# MOTOR_DRIVER.net
KiCad netlist of a schematic drawn in EAGLE
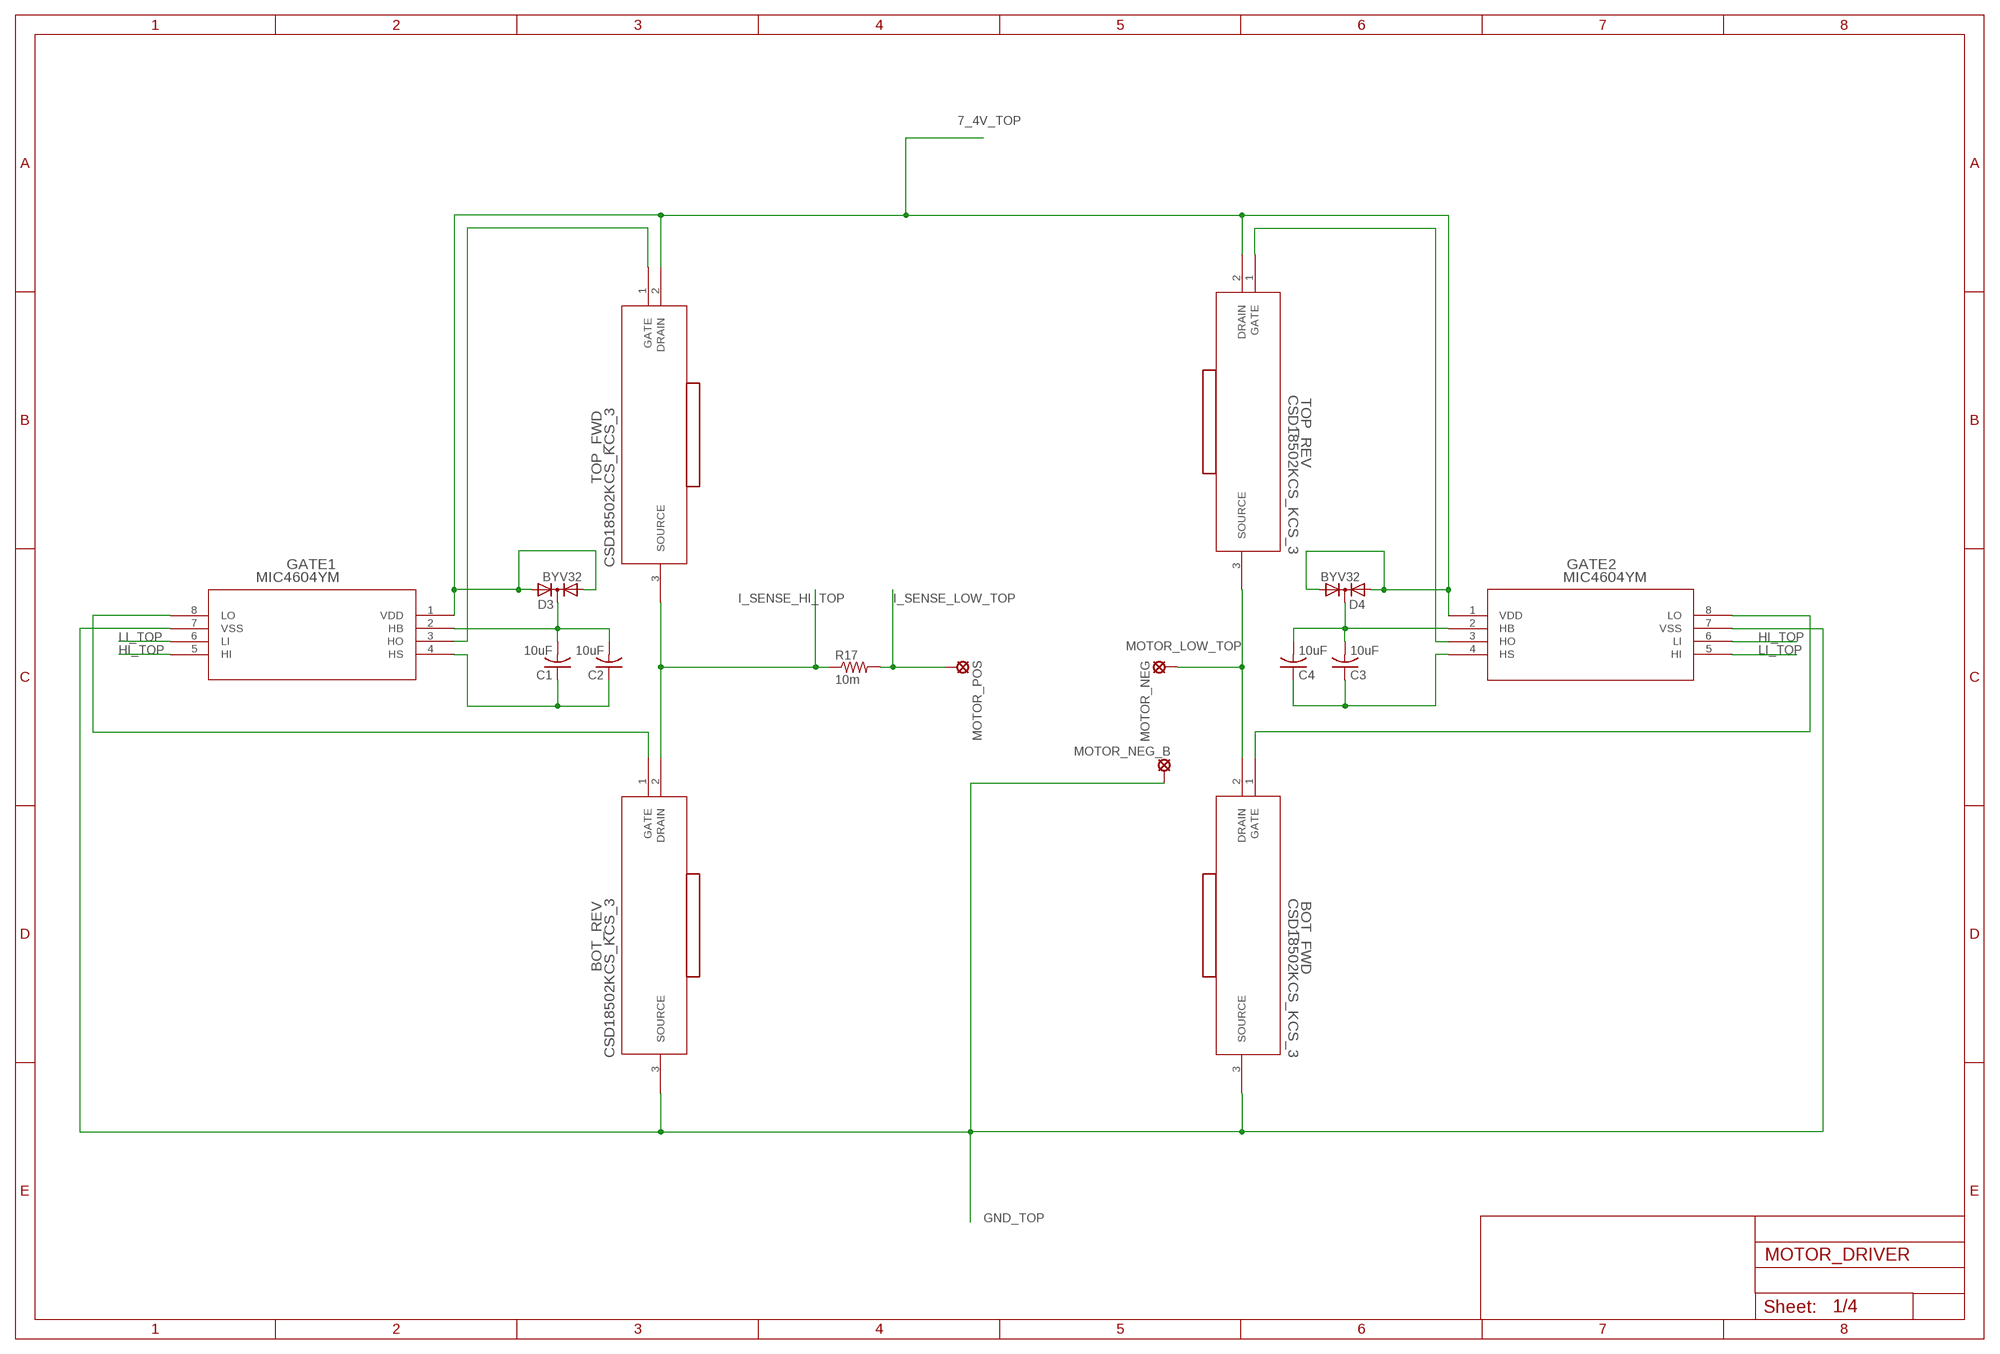
[diagram p0: schematic, sheet 1]
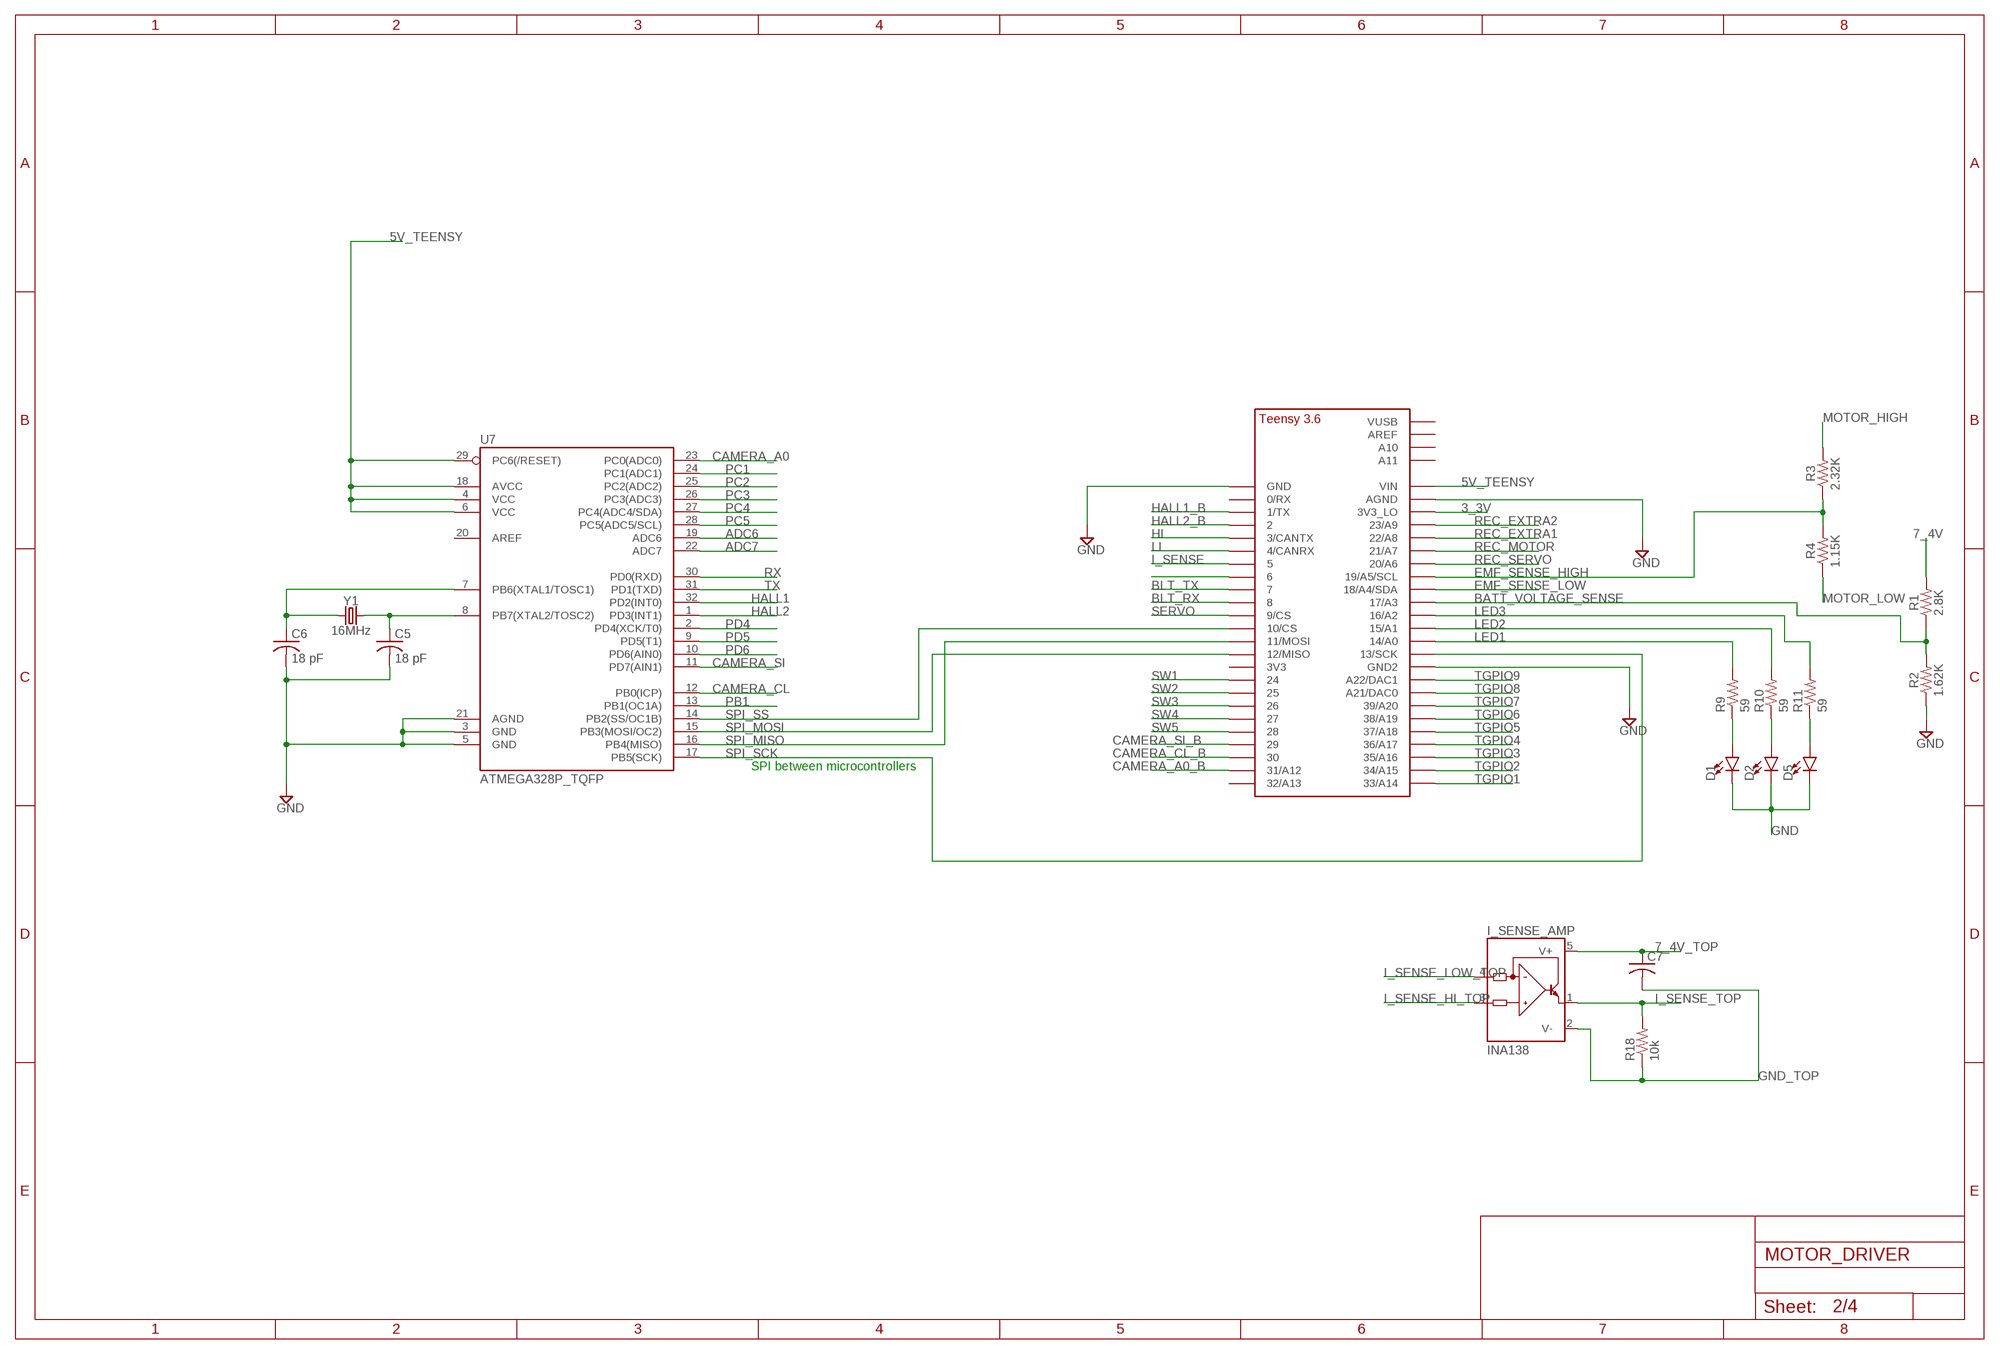
[diagram p1: schematic, sheet 2]
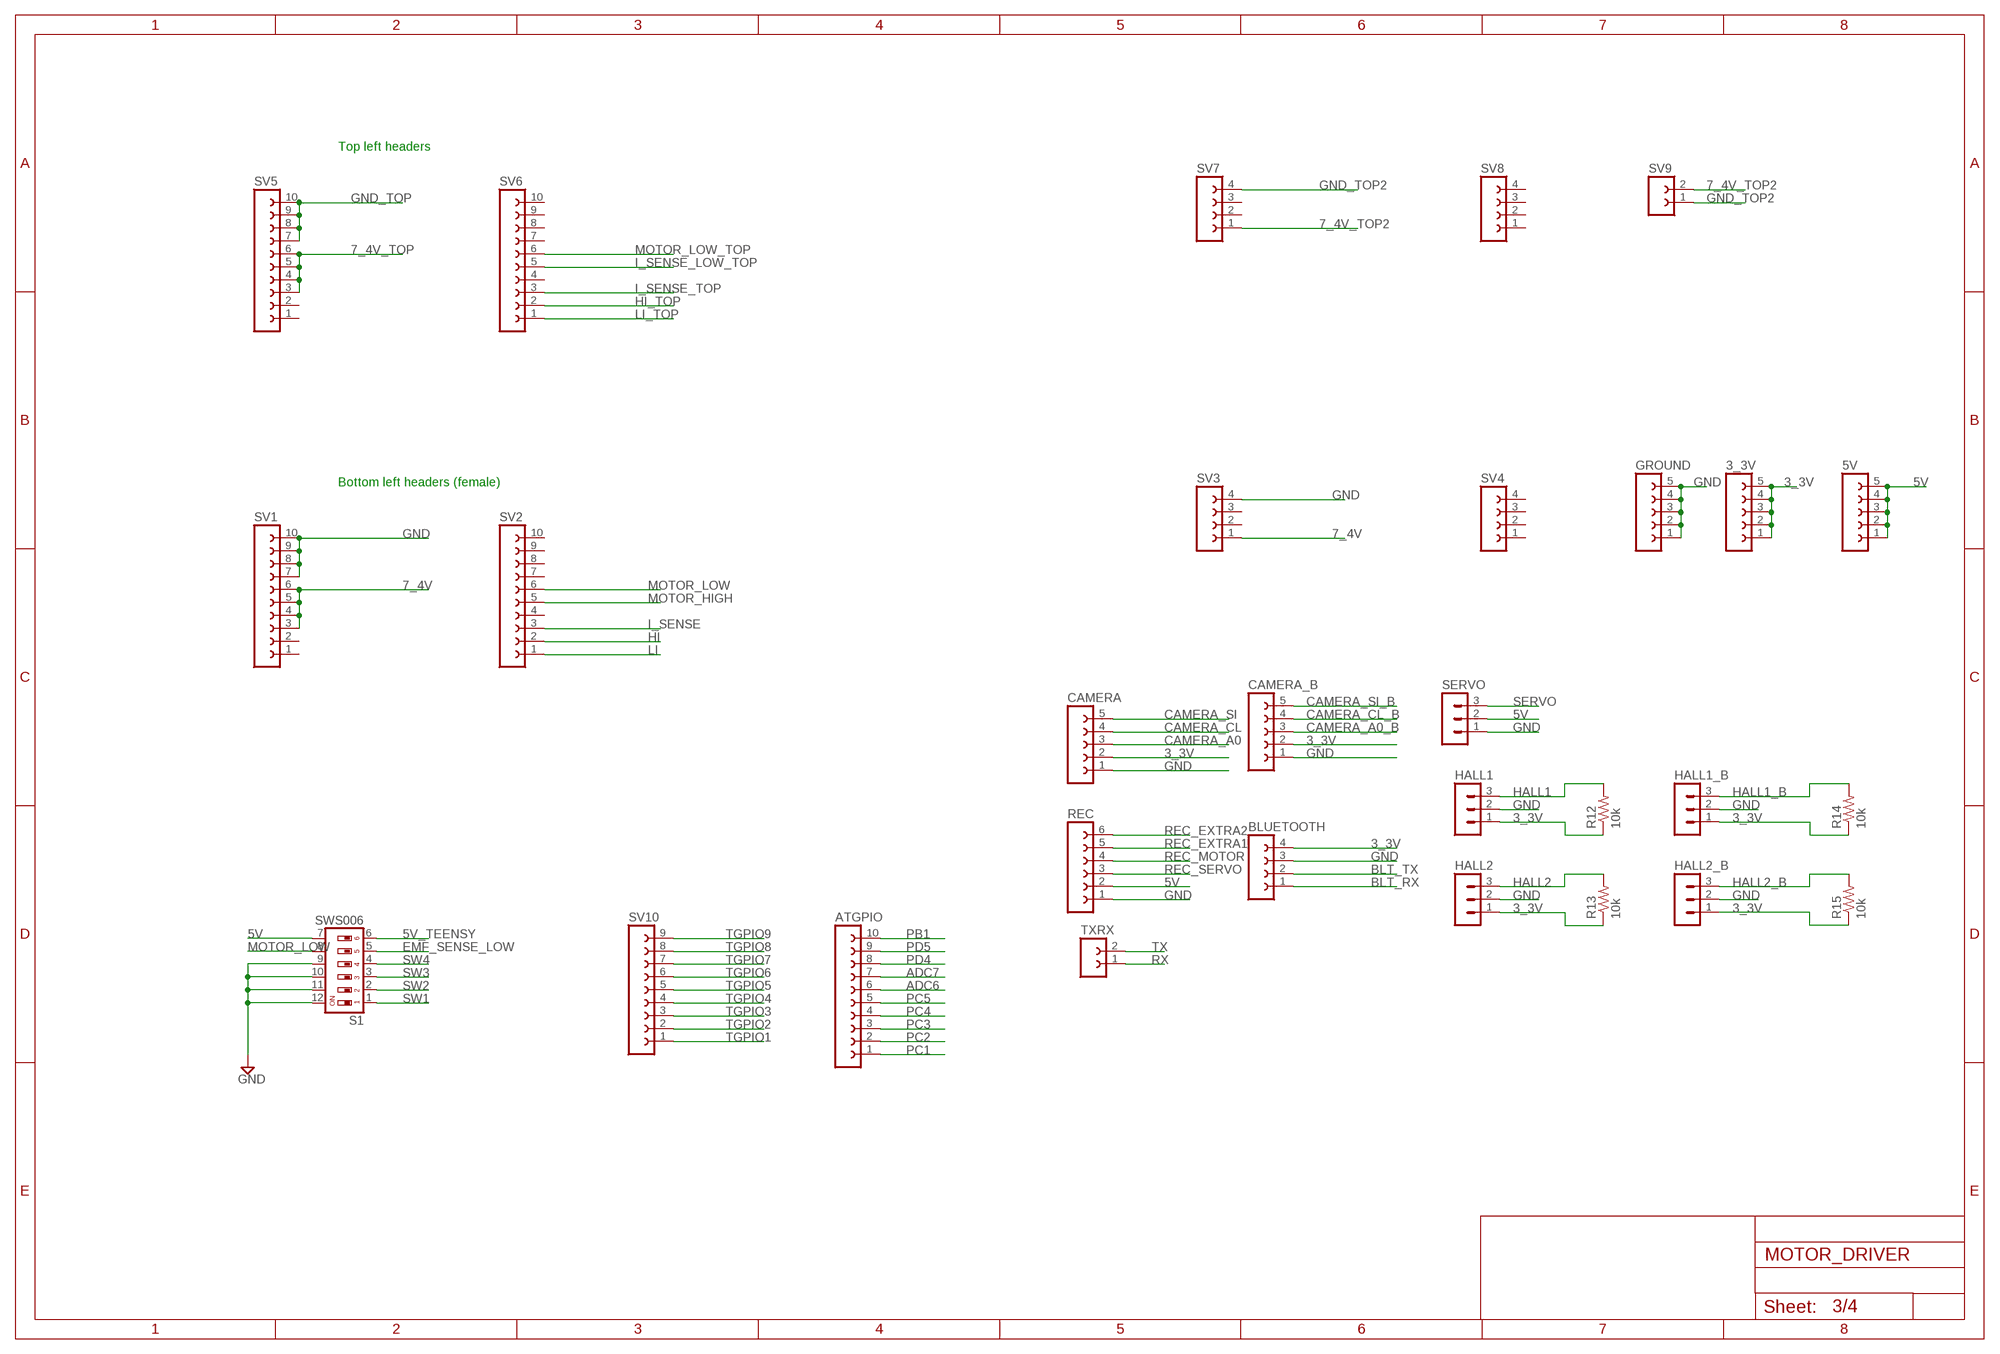
[diagram p2: schematic, sheet 3]
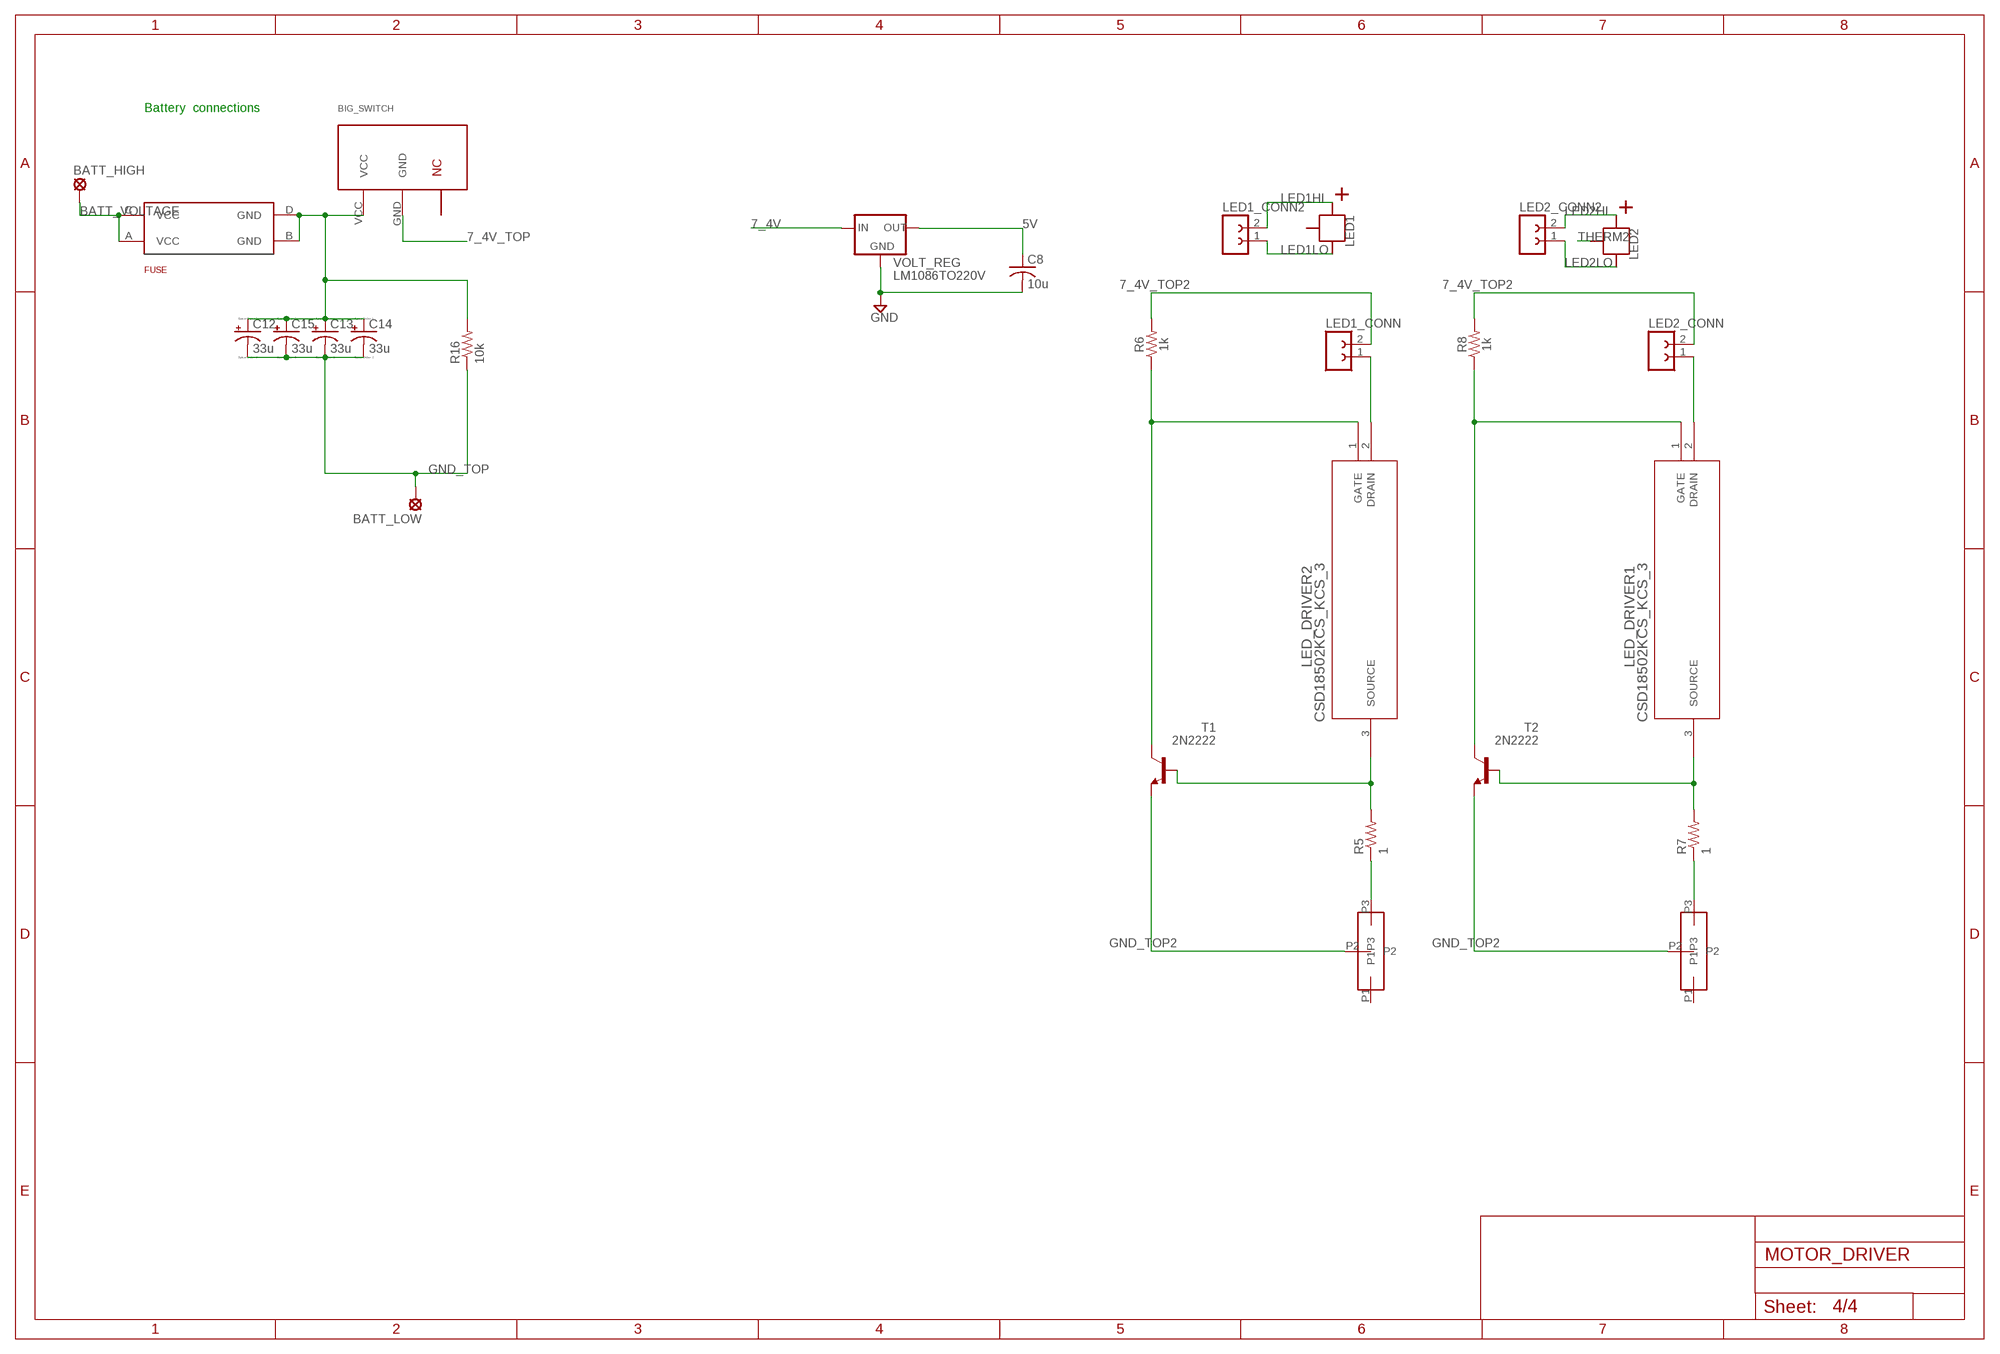
[diagram p3: schematic, sheet 4]

(export (version "E")
  (design (tool "Eeschema 10.0.6"))
  (components
    (comp (ref "BOT_FWD")
      (value "CSD18502KCS_KCS_3")
      (footprint "eagle-import:KCS3")
      (fields
        (field (name "DIGIKEY_PART_NUMBER") "296-35013-ND")
        (field (name "MANUFACTURER") "Texas Instruments")
        (field (name "MANUFACTURER_PART_NUMBER") "CSD18533KCS")
      )
      (libsource (lib "eagle-import") (part "CSD18502KCS_KCS_3"))
    )
    (comp (ref "BOT_REV")
      (value "CSD18502KCS_KCS_3")
      (footprint "eagle-import:KCS3")
      (fields
        (field (name "DIGIKEY_PART_NUMBER") "296-35013-ND")
        (field (name "MANUFACTURER") "Texas Instruments")
        (field (name "MANUFACTURER_PART_NUMBER") "CSD18533KCS")
      )
      (libsource (lib "eagle-import") (part "CSD18502KCS_KCS_3"))
    )
    (comp (ref "C1")
      (value "10uF")
      (footprint "eagle-import:C025-050X050")
      (libsource (lib "eagle-import") (part "resistor_C-US025-050X050"))
    )
    (comp (ref "C2")
      (value "10uF")
      (footprint "eagle-import:C025-050X050")
      (libsource (lib "eagle-import") (part "resistor_C-US025-050X050"))
    )
    (comp (ref "C3")
      (value "10uF")
      (footprint "eagle-import:C025-050X050")
      (libsource (lib "eagle-import") (part "resistor_C-US025-050X050"))
    )
    (comp (ref "C4")
      (value "10uF")
      (footprint "eagle-import:C025-050X050")
      (libsource (lib "eagle-import") (part "resistor_C-US025-050X050"))
    )
    (comp (ref "D3")
      (value "BYV32")
      (footprint "eagle-import:TO220ABS")
      (libsource (lib "eagle-import") (part "BYV32"))
    )
    (comp (ref "D4")
      (value "BYV32")
      (footprint "eagle-import:TO220ABS")
      (libsource (lib "eagle-import") (part "BYV32"))
    )
    (comp (ref "GATE1")
      (value "MIC4604YM")
      (footprint "eagle-import:SOIC-8_M")
      (fields
        (field (name "DIGIKEY_PART_NUMBER") "576-4395-1-ND")
        (field (name "MANUFACTURER") "Microchip")
        (field (name "MANUFACTURER_PART_NUMBER") "MIC4604YM-T5")
      )
      (libsource (lib "eagle-import") (part "MIC4604YM"))
    )
    (comp (ref "GATE2")
      (value "MIC4604YM")
      (footprint "eagle-import:SOIC-8_M")
      (fields
        (field (name "DIGIKEY_PART_NUMBER") "576-4395-1-ND")
        (field (name "MANUFACTURER") "Microchip")
        (field (name "MANUFACTURER_PART_NUMBER") "MIC4604YM-T5")
      )
      (libsource (lib "eagle-import") (part "MIC4604YM"))
    )
    (comp (ref "MOTOR_NEG")
      (value "SE14")
      (footprint "eagle-import:SE14")
      (libsource (lib "eagle-import") (part "SE14"))
    )
    (comp (ref "MOTOR_NEG_B")
      (value "SE14")
      (footprint "eagle-import:SE14")
      (libsource (lib "eagle-import") (part "SE14"))
    )
    (comp (ref "MOTOR_POS")
      (value "SE14")
      (footprint "eagle-import:SE14")
      (libsource (lib "eagle-import") (part "SE14"))
    )
    (comp (ref "R17")
      (value "10m")
      (footprint "eagle-import:R2512")
      (libsource (lib "eagle-import") (part "R-US_R2512"))
    )
    (comp (ref "TOP_FWD")
      (value "CSD18502KCS_KCS_3")
      (footprint "eagle-import:KCS3")
      (fields
        (field (name "DIGIKEY_PART_NUMBER") "296-35013-ND")
        (field (name "MANUFACTURER") "Texas Instruments")
        (field (name "MANUFACTURER_PART_NUMBER") "CSD18533KCS")
      )
      (libsource (lib "eagle-import") (part "CSD18502KCS_KCS_3"))
    )
    (comp (ref "TOP_REV")
      (value "CSD18502KCS_KCS_3")
      (footprint "eagle-import:KCS3")
      (fields
        (field (name "DIGIKEY_PART_NUMBER") "296-35013-ND")
        (field (name "MANUFACTURER") "Texas Instruments")
        (field (name "MANUFACTURER_PART_NUMBER") "CSD18533KCS")
      )
      (libsource (lib "eagle-import") (part "CSD18502KCS_KCS_3"))
    )
    (comp (ref "U$2")
      (value "HEATSINK")
      (footprint "eagle-import:HEATSINK")
      (fields
        (field (name "DIGIKEY_PART_NUMBER") "HS112-ND")
        (field (name "MANUFACTURER") "Aavid Thermalloy")
        (field (name "MANUFACTURER_PART_NUMBER") "507002B00000G")
      )
      (libsource (lib "eagle-import") (part "HEATSINK"))
    )
    (comp (ref "U$4")
      (value "HEATSINK")
      (footprint "eagle-import:HEATSINK")
      (fields
        (field (name "DIGIKEY_PART_NUMBER") "HS112-ND")
        (field (name "MANUFACTURER") "Aavid Thermalloy")
        (field (name "MANUFACTURER_PART_NUMBER") "507002B00000G")
      )
      (libsource (lib "eagle-import") (part "HEATSINK"))
    )
    (comp (ref "U$5")
      (value "HEATSINK")
      (footprint "eagle-import:HEATSINK")
      (fields
        (field (name "DIGIKEY_PART_NUMBER") "HS112-ND")
        (field (name "MANUFACTURER") "Aavid Thermalloy")
        (field (name "MANUFACTURER_PART_NUMBER") "507002B00000G")
      )
      (libsource (lib "eagle-import") (part "HEATSINK"))
    )
    (comp (ref "U$6")
      (value "HEATSINK")
      (footprint "eagle-import:HEATSINK")
      (fields
        (field (name "DIGIKEY_PART_NUMBER") "HS112-ND")
        (field (name "MANUFACTURER") "Aavid Thermalloy")
        (field (name "MANUFACTURER_PART_NUMBER") "507002B00000G")
      )
      (libsource (lib "eagle-import") (part "HEATSINK"))
    )
    (comp (ref "BATT_HIGH")
      (value "SE14")
      (footprint "eagle-import:SE14")
      (libsource (lib "eagle-import") (part "SE14"))
    )
    (comp (ref "BATT_LOW")
      (value "SE14")
      (footprint "eagle-import:SE14")
      (libsource (lib "eagle-import") (part "SE14"))
    )
    (comp (ref "BIG_SWITCH")
      (value "BIGSWITCH")
      (footprint "eagle-import:BIGSWITCH")
      (fields
        (field (name "DIGIKEY_PART_NUMBER") "CW106-ND")
        (field (name "MANUFACTURER") "CW Industries")
        (field (name "MANUFACTURER_PART_NUMBER") "GRB238B801BR1")
      )
      (libsource (lib "eagle-import") (part "BIGSWITCH"))
    )
    (comp (ref "C8")
      (value "10u")
      (footprint "eagle-import:C0805")
      (libsource (lib "eagle-import") (part "C-USC0805"))
    )
    (comp (ref "C12")
      (value "33u")
      (footprint "eagle-import:153CLV-1010")
      (libsource (lib "eagle-import") (part "CPOL-US153CLV-1010"))
    )
    (comp (ref "C13")
      (value "33u")
      (footprint "eagle-import:153CLV-1010")
      (libsource (lib "eagle-import") (part "CPOL-US153CLV-1010"))
    )
    (comp (ref "C14")
      (value "33u")
      (footprint "eagle-import:153CLV-1010")
      (libsource (lib "eagle-import") (part "CPOL-US153CLV-1010"))
    )
    (comp (ref "C15")
      (value "33u")
      (footprint "eagle-import:153CLV-1010")
      (libsource (lib "eagle-import") (part "CPOL-US153CLV-1010"))
    )
    (comp (ref "FUSE")
      (value "FUSEHOLDER3588")
      (footprint "eagle-import:FUSEHOLDER3588")
      (fields
        (field (name "DIGIKEY_PART_NUMBER") "F4989-ND")
        (field (name "MANUFACTURER") "Littelfuse Inc.")
        (field (name "MANUFACTURER_PART_NUMBER") "0891010.NXS")
      )
      (libsource (lib "eagle-import") (part "FUSEHOLDER3588"))
    )
    (comp (ref "LED1")
      (value "CREE_XP")
      (footprint "eagle-import:XP")
      (libsource (lib "eagle-import") (part "CREE_XP"))
    )
    (comp (ref "LED1_CONN")
      (value "FE02-1")
      (footprint "eagle-import:FE02-1")
      (libsource (lib "eagle-import") (part "FE02-1"))
    )
    (comp (ref "LED1_CONN2")
      (value "FE02-1")
      (footprint "eagle-import:FE02-1")
      (libsource (lib "eagle-import") (part "FE02-1"))
    )
    (comp (ref "LED2")
      (value "CREE_XP")
      (footprint "eagle-import:XP")
      (libsource (lib "eagle-import") (part "CREE_XP"))
    )
    (comp (ref "LED2_CONN")
      (value "FE02-1")
      (footprint "eagle-import:FE02-1")
      (libsource (lib "eagle-import") (part "FE02-1"))
    )
    (comp (ref "LED2_CONN2")
      (value "FE02-1")
      (footprint "eagle-import:FE02-1")
      (libsource (lib "eagle-import") (part "FE02-1"))
    )
    (comp (ref "LED_DRIVER1")
      (value "CSD18502KCS_KCS_3")
      (footprint "eagle-import:KCS3")
      (fields
        (field (name "DIGIKEY_PART_NUMBER") "296-35013-ND")
        (field (name "MANUFACTURER") "Texas Instruments")
        (field (name "MANUFACTURER_PART_NUMBER") "CSD18533KCS")
      )
      (libsource (lib "eagle-import") (part "CSD18502KCS_KCS_3"))
    )
    (comp (ref "LED_DRIVER2")
      (value "CSD18502KCS_KCS_3")
      (footprint "eagle-import:KCS3")
      (fields
        (field (name "DIGIKEY_PART_NUMBER") "296-35013-ND")
        (field (name "MANUFACTURER") "Texas Instruments")
        (field (name "MANUFACTURER_PART_NUMBER") "CSD18533KCS")
      )
      (libsource (lib "eagle-import") (part "CSD18502KCS_KCS_3"))
    )
    (comp (ref "R5")
      (value "1")
      (footprint "eagle-import:R2512")
      (libsource (lib "eagle-import") (part "R-US_R2512"))
    )
    (comp (ref "R6")
      (value "1k")
      (footprint "eagle-import:AXIAL-0.3")
      (libsource (lib "eagle-import") (part "1KOHM-HORIZ-1/4W-1%"))
    )
    (comp (ref "R7")
      (value "1")
      (footprint "eagle-import:R2512")
      (libsource (lib "eagle-import") (part "R-US_R2512"))
    )
    (comp (ref "R8")
      (value "1k")
      (footprint "eagle-import:AXIAL-0.3")
      (libsource (lib "eagle-import") (part "1KOHM-HORIZ-1/4W-1%"))
    )
    (comp (ref "R16")
      (value "10k")
      (footprint "eagle-import:R0603")
      (libsource (lib "eagle-import") (part "resistor_R-US_R0603"))
    )
    (comp (ref "T1")
      (value "2N2222")
      (footprint "eagle-import:TO18")
      (libsource (lib "eagle-import") (part "2N2222"))
    )
    (comp (ref "T2")
      (value "2N2222")
      (footprint "eagle-import:TO18")
      (libsource (lib "eagle-import") (part "2N2222"))
    )
    (comp (ref "U$3")
      (value "POT")
      (footprint "eagle-import:POT")
      (libsource (lib "eagle-import") (part "POT"))
    )
    (comp (ref "U$7")
      (value "POT")
      (footprint "eagle-import:POT")
      (libsource (lib "eagle-import") (part "POT"))
    )
    (comp (ref "VOLT_REG")
      (value "LM1086TO220V")
      (footprint "eagle-import:TO220S")
      (fields
        (field (name "DIGIKEY_PART_NUMBER") "LM1086IT-5.0/NOPB-ND")
        (field (name "MANUFACTURER") "Texas Instruments")
        (field (name "MANUFACTURER_PART_NUMBER") "LM1086IT-5.0/NOPB")
      )
      (libsource (lib "eagle-import") (part "LM1086TO220V"))
    )
    (comp (ref "3_3V")
      (value "FE05-1")
      (footprint "eagle-import:FE05-1")
      (libsource (lib "eagle-import") (part "FE05-1"))
    )
    (comp (ref "5V")
      (value "FE05-1")
      (footprint "eagle-import:FE05-1")
      (libsource (lib "eagle-import") (part "FE05-1"))
    )
    (comp (ref "ATGPIO")
      (value "FE10-1")
      (footprint "eagle-import:FE10")
      (libsource (lib "eagle-import") (part "FE10-1"))
    )
    (comp (ref "BLUETOOTH")
      (value "FE04-1")
      (footprint "eagle-import:FE04-1")
      (fields
        (field (name "MANUFACTURER") "HC Information Technology")
        (field (name "MANUFACTURER_PART_NUMBER") "HC-06")
      )
      (libsource (lib "eagle-import") (part "FE04-1"))
    )
    (comp (ref "CAMERA")
      (value "FE05-1")
      (footprint "eagle-import:FE05-1")
      (fields
        (field (name "DIGIKEY_PART_NUMBER") "28317-ND")
        (field (name "MANUFACTURER") "Parallax")
        (field (name "MANUFACTURER_PART_NUMBER") "28317")
      )
      (libsource (lib "eagle-import") (part "FE05-1"))
    )
    (comp (ref "CAMERA_B")
      (value "FE05-1")
      (footprint "eagle-import:FE05-1")
      (fields
        (field (name "DIGIKEY_PART_NUMBER") "28317-ND")
        (field (name "MANUFACTURER") "Parallax")
        (field (name "MANUFACTURER_PART_NUMBER") "28317")
      )
      (libsource (lib "eagle-import") (part "FE05-1"))
    )
    (comp (ref "GROUND")
      (value "FE05-1")
      (footprint "eagle-import:FE05-1")
      (libsource (lib "eagle-import") (part "FE05-1"))
    )
    (comp (ref "HALL1")
      (value "MA03-1")
      (footprint "eagle-import:MA03-1")
      (fields
        (field (name "DIGIKEY_PART_NUMBER") "US1881LUA-AAA-000-BU-ND")
        (field (name "MANUFACTURER") "Melexis Technologies NV")
        (field (name "MANUFACTURER_PART_NUMBER") "US1881LUA-AAA-000-BU")
      )
      (libsource (lib "eagle-import") (part "MA03-1"))
    )
    (comp (ref "HALL1_B")
      (value "MA03-1")
      (footprint "eagle-import:MA03-1")
      (fields
        (field (name "DIGIKEY_PART_NUMBER") "US1881LUA-AAA-000-BU-ND")
        (field (name "MANUFACTURER") "Melexis Technologies NV")
        (field (name "MANUFACTURER_PART_NUMBER") "US1881LUA-AAA-000-BU")
      )
      (libsource (lib "eagle-import") (part "MA03-1"))
    )
    (comp (ref "HALL2")
      (value "MA03-1")
      (footprint "eagle-import:MA03-1")
      (fields
        (field (name "DIGIKEY_PART_NUMBER") "US1881LUA-AAA-000-BU-ND")
        (field (name "MANUFACTURER") "Melexis Technologies NV")
        (field (name "MANUFACTURER_PART_NUMBER") "US1881LUA-AAA-000-BU")
      )
      (libsource (lib "eagle-import") (part "MA03-1"))
    )
    (comp (ref "HALL2_B")
      (value "MA03-1")
      (footprint "eagle-import:MA03-1")
      (fields
        (field (name "DIGIKEY_PART_NUMBER") "US1881LUA-AAA-000-BU-ND")
        (field (name "MANUFACTURER") "Melexis Technologies NV")
        (field (name "MANUFACTURER_PART_NUMBER") "US1881LUA-AAA-000-BU")
      )
      (libsource (lib "eagle-import") (part "MA03-1"))
    )
    (comp (ref "R12")
      (value "10k")
      (footprint "eagle-import:R0603")
      (libsource (lib "eagle-import") (part "resistor_R-US_R0603"))
    )
    (comp (ref "R13")
      (value "10k")
      (footprint "eagle-import:R0603")
      (libsource (lib "eagle-import") (part "resistor_R-US_R0603"))
    )
    (comp (ref "R14")
      (value "10k")
      (footprint "eagle-import:R0603")
      (libsource (lib "eagle-import") (part "resistor_R-US_R0603"))
    )
    (comp (ref "R15")
      (value "10k")
      (footprint "eagle-import:R0603")
      (libsource (lib "eagle-import") (part "resistor_R-US_R0603"))
    )
    (comp (ref "REC")
      (value "FE06-1")
      (footprint "eagle-import:FE06")
      (libsource (lib "eagle-import") (part "FE06-1"))
    )
    (comp (ref "S1")
      (value "SWS006")
      (footprint "eagle-import:SMS-006")
      (fields
        (field (name "DIGIKEY_PART_NUMBER") "CT2196MST-ND")
        (field (name "MANUFACTURER") "CTS Electrocomponents")
        (field (name "MANUFACTURER_PART_NUMBER") "219-6MST")
      )
      (libsource (lib "eagle-import") (part "SWS006"))
    )
    (comp (ref "SERVO")
      (value "MA03-1")
      (footprint "eagle-import:MA03-1")
      (fields (field (name "MANUFACTURER") "TrackStar") (field (name "MANUFACTURER_PART_NUMBER") "TS-P12S"))
      (libsource (lib "eagle-import") (part "MA03-1"))
    )
    (comp (ref "SV1")
      (value "FE10-1")
      (footprint "eagle-import:FE10")
      (libsource (lib "eagle-import") (part "FE10-1"))
    )
    (comp (ref "SV2")
      (value "FE10-1")
      (footprint "eagle-import:FE10")
      (libsource (lib "eagle-import") (part "FE10-1"))
    )
    (comp (ref "SV3")
      (value "FE04-1")
      (footprint "eagle-import:FE04-1")
      (libsource (lib "eagle-import") (part "FE04-1"))
    )
    (comp (ref "SV4")
      (value "FE04-1")
      (footprint "eagle-import:FE04-1")
      (libsource (lib "eagle-import") (part "FE04-1"))
    )
    (comp (ref "SV5")
      (value "FE10-1")
      (footprint "eagle-import:FE10")
      (libsource (lib "eagle-import") (part "FE10-1"))
    )
    (comp (ref "SV6")
      (value "FE10-1")
      (footprint "eagle-import:FE10")
      (libsource (lib "eagle-import") (part "FE10-1"))
    )
    (comp (ref "SV7")
      (value "FE04-1")
      (footprint "eagle-import:FE04-1")
      (libsource (lib "eagle-import") (part "FE04-1"))
    )
    (comp (ref "SV8")
      (value "FE04-1")
      (footprint "eagle-import:FE04-1")
      (libsource (lib "eagle-import") (part "FE04-1"))
    )
    (comp (ref "SV9")
      (value "FE02-1")
      (footprint "eagle-import:FE02-1")
      (libsource (lib "eagle-import") (part "FE02-1"))
    )
    (comp (ref "SV10")
      (value "FE09-1")
      (footprint "eagle-import:FE09")
      (libsource (lib "eagle-import") (part "FE09-1"))
    )
    (comp (ref "TXRX")
      (value "FE02-1")
      (footprint "eagle-import:FE02-1")
      (libsource (lib "eagle-import") (part "FE02-1"))
    )
    (comp (ref "C5")
      (value "18 pF")
      (footprint "eagle-import:C025-024X044")
      (libsource (lib "eagle-import") (part "resistor_C-US025-024X044"))
    )
    (comp (ref "C6")
      (value "18 pF")
      (footprint "eagle-import:C025-024X044")
      (libsource (lib "eagle-import") (part "resistor_C-US025-024X044"))
    )
    (comp (ref "C7")
      (value "C-USC0603")
      (footprint "eagle-import:C0603")
      (libsource (lib "eagle-import") (part "resistor_C-USC0603"))
    )
    (comp (ref "D1")
      (value "LED0603")
      (footprint "eagle-import:LED-0603")
      (libsource (lib "eagle-import") (part "LED0603"))
    )
    (comp (ref "D2")
      (value "LED0603")
      (footprint "eagle-import:LED-0603")
      (libsource (lib "eagle-import") (part "LED0603"))
    )
    (comp (ref "D5")
      (value "LED0603")
      (footprint "eagle-import:LED-0603")
      (libsource (lib "eagle-import") (part "LED0603"))
    )
    (comp (ref "I_SENSE_AMP")
      (value "INA138")
      (footprint "eagle-import:SOT23-5")
      (fields
        (field (name "DIGIKEY_PART_NUMBER") "INA138NACT-ND")
        (field (name "MANUFACTURER") "Texas Instruments")
        (field (name "MANUFACTURER_PART_NUMBER") "INA138NA/250")
      )
      (libsource (lib "eagle-import") (part "INA138"))
    )
    (comp (ref "R1")
      (value "2.8K")
      (footprint "eagle-import:0805")
      (fields
        (field (name "DIGIKEY_PART_NUMBER") "311-2.80KCRCT-ND")
        (field (name "MANUFACTURER") "Yageo")
        (field (name "MANUFACTURER_PART_NUMBER") "RC0805FR-072K8L")
      )
      (libsource (lib "eagle-import") (part "0.3OHM-0805-1/8W-1%"))
    )
    (comp (ref "R2")
      (value "1.62K")
      (footprint "eagle-import:0805")
      (fields
        (field (name "DIGIKEY_PART_NUMBER") "311-1.62KCRCT-ND")
        (field (name "MANUFACTURER") "Yageo")
        (field (name "MANUFACTURER_PART_NUMBER") "RC0805FR-071K62L")
      )
      (libsource (lib "eagle-import") (part "0.3OHM-0805-1/8W-1%"))
    )
    (comp (ref "R3")
      (value "2.32K")
      (footprint "eagle-import:0805")
      (fields
        (field (name "DIGIKEY_PART_NUMBER") "311-2.32KCRCT-ND")
        (field (name "MANUFACTURER") "Yageo")
        (field (name "MANUFACTURER_PART_NUMBER") "RC0805FR-072K32L")
      )
      (libsource (lib "eagle-import") (part "0.3OHM-0805-1/8W-1%"))
    )
    (comp (ref "R4")
      (value "1.15K")
      (footprint "eagle-import:0805")
      (fields
        (field (name "DIGIKEY_PART_NUMBER") "311-1.15KCRCT-ND")
        (field (name "MANUFACTURER") "Yageo")
        (field (name "MANUFACTURER_PART_NUMBER") "RC0805FR-071K15L")
      )
      (libsource (lib "eagle-import") (part "0.3OHM-0805-1/8W-1%"))
    )
    (comp (ref "R9")
      (value "59")
      (footprint "eagle-import:R0805")
      (libsource (lib "eagle-import") (part "R-US_R0805"))
    )
    (comp (ref "R10")
      (value "59")
      (footprint "eagle-import:R0805")
      (libsource (lib "eagle-import") (part "R-US_R0805"))
    )
    (comp (ref "R11")
      (value "59")
      (footprint "eagle-import:R0805")
      (libsource (lib "eagle-import") (part "R-US_R0805"))
    )
    (comp (ref "R18")
      (value "10k")
      (footprint "eagle-import:R0603")
      (libsource (lib "eagle-import") (part "R-US_R0603"))
    )
    (comp (ref "U$1")
      (value "TEENSY_3.5/3.6_BASIC")
      (footprint "eagle-import:TEENSY_3.5_3.6_BASIC")
      (fields
        (field (name "DIGIKEY_PART_NUMBER") "1568-1443-ND")
        (field (name "MANUFACTURER") "SparkFun Electronics")
        (field (name "MANUFACTURER_PART_NUMBER") "DEV-14055")
      )
      (libsource (lib "eagle-import") (part "TEENSY_3.5/3.6_BASIC"))
    )
    (comp (ref "U7")
      (value "ATMEGA328P_TQFP")
      (footprint "eagle-import:TQFP32-08")
      (fields
        (field (name "DIGIKEY_PART_NUMBER") "ATMEGA328PB-AU-ND")
        (field (name "MANUFACTURER") "Microchip Technology")
        (field (name "MANUFACTURER_PART_NUMBER") "ATMEGA328PB-AU")
      )
      (libsource (lib "eagle-import") (part "ATMEGA328P_TQFP"))
    )
    (comp (ref "Y1")
      (value "16MHz")
      (footprint "eagle-import:HC49US")
      (fields
        (field (name "DIGIKEY_PART_NUMBER") "887-2425-1-ND")
        (field (name "MANUFACTURER") "TXC CORPORATION")
        (field (name "MANUFACTURER_PART_NUMBER") "9C-16.000MBBK-T")
      )
      (libsource (lib "eagle-import") (part "CRYSTAL-16MHZPTH-HC49US"))
    )
  )
  (nets
    (net (code "1") (name "3_3V") (class "Default")
      (node (ref "3_3V") (pin "1") (pinfunction "1_1") (pintype "passive"))
      (node (ref "3_3V") (pin "2") (pinfunction "2_2") (pintype "passive"))
      (node (ref "3_3V") (pin "3") (pinfunction "3_3") (pintype "passive"))
      (node (ref "3_3V") (pin "4") (pinfunction "4_4") (pintype "passive"))
      (node (ref "3_3V") (pin "5") (pinfunction "5_5") (pintype "passive"))
      (node (ref "BLUETOOTH") (pin "4") (pinfunction "4_4") (pintype "passive"))
      (node (ref "CAMERA") (pin "2") (pinfunction "2_2") (pintype "passive"))
      (node (ref "CAMERA_B") (pin "2") (pinfunction "2_2") (pintype "passive"))
      (node (ref "HALL1") (pin "1") (pinfunction "1_1") (pintype "passive"))
      (node (ref "HALL1_B") (pin "1") (pinfunction "1_1") (pintype "passive"))
      (node (ref "HALL2") (pin "1") (pinfunction "1_1") (pintype "passive"))
      (node (ref "HALL2_B") (pin "1") (pinfunction "1_1") (pintype "passive"))
      (node (ref "R12") (pin "1") (pinfunction "1_1") (pintype "passive"))
      (node (ref "R13") (pin "1") (pinfunction "1_1") (pintype "passive"))
      (node (ref "R14") (pin "1") (pinfunction "1_1") (pintype "passive"))
      (node (ref "R15") (pin "1") (pinfunction "1_1") (pintype "passive"))
      (node (ref "U$1") (pin "3V3_LO") (pinfunction "3V3_LO_3V3_LO") (pintype "bidirectional"))
    )
    (net (code "2") (name "5V") (class "Default")
      (node (ref "5V") (pin "1") (pinfunction "1_1") (pintype "passive"))
      (node (ref "5V") (pin "2") (pinfunction "2_2") (pintype "passive"))
      (node (ref "5V") (pin "3") (pinfunction "3_3") (pintype "passive"))
      (node (ref "5V") (pin "4") (pinfunction "4_4") (pintype "passive"))
      (node (ref "5V") (pin "5") (pinfunction "5_5") (pintype "passive"))
      (node (ref "C8") (pin "1") (pinfunction "1_1") (pintype "passive"))
      (node (ref "REC") (pin "2") (pinfunction "2_2") (pintype "passive"))
      (node (ref "S1") (pin "7") (pinfunction "7_7") (pintype "passive"))
      (node (ref "SERVO") (pin "2") (pinfunction "2_2") (pintype "passive"))
      (node (ref "VOLT_REG") (pin "2") (pinfunction "OUT_2") (pintype "passive"))
    )
    (net (code "3") (name "5V_TEENSY") (class "Default")
      (node (ref "S1") (pin "6") (pinfunction "6_6") (pintype "passive"))
      (node (ref "U$1") (pin "VIN") (pinfunction "VIN_VIN") (pintype "bidirectional"))
      (node (ref "U7") (pin "18") (pinfunction "AVCC_18") (pintype "bidirectional"))
      (node (ref "U7") (pin "29") (pinfunction "PC6(/RESET)_29") (pintype "bidirectional"))
      (node (ref "U7") (pin "4") (pinfunction "VCC_4") (pintype "bidirectional"))
      (node (ref "U7") (pin "6") (pinfunction "VCC_6") (pintype "bidirectional"))
    )
    (net (code "4") (name "7_4V") (class "Default")
      (node (ref "R1") (pin "2") (pinfunction "2_2") (pintype "passive"))
      (node (ref "SV1") (pin "3") (pinfunction "3_3") (pintype "passive"))
      (node (ref "SV1") (pin "4") (pinfunction "4_4") (pintype "passive"))
      (node (ref "SV1") (pin "5") (pinfunction "5_5") (pintype "passive"))
      (node (ref "SV1") (pin "6") (pinfunction "6_6") (pintype "passive"))
      (node (ref "SV3") (pin "1") (pinfunction "1_1") (pintype "passive"))
      (node (ref "VOLT_REG") (pin "3") (pinfunction "IN_3") (pintype "input"))
    )
    (net (code "5") (name "7_4V_TOP") (class "Default")
      (node (ref "BIG_SWITCH") (pin "GND") (pinfunction "GND_GND") (pintype "power_in"))
      (node (ref "C7") (pin "1") (pinfunction "1_1") (pintype "passive"))
      (node (ref "D3") (pin "A1") (pinfunction "A1_A1") (pintype "passive"))
      (node (ref "D3") (pin "A2") (pinfunction "A2_A2") (pintype "passive"))
      (node (ref "D4") (pin "A1") (pinfunction "A1_A1") (pintype "passive"))
      (node (ref "D4") (pin "A2") (pinfunction "A2_A2") (pintype "passive"))
      (node (ref "GATE1") (pin "1") (pinfunction "VDD_1") (pintype "power_in"))
      (node (ref "GATE2") (pin "1") (pinfunction "VDD_1") (pintype "power_in"))
      (node (ref "I_SENSE_AMP") (pin "5") (pinfunction "V+_5") (pintype "power_in"))
      (node (ref "SV5") (pin "3") (pinfunction "3_3") (pintype "passive"))
      (node (ref "SV5") (pin "4") (pinfunction "4_4") (pintype "passive"))
      (node (ref "SV5") (pin "5") (pinfunction "5_5") (pintype "passive"))
      (node (ref "SV5") (pin "6") (pinfunction "6_6") (pintype "passive"))
      (node (ref "TOP_FWD") (pin "2") (pinfunction "DRAIN_2") (pintype "passive"))
      (node (ref "TOP_REV") (pin "2") (pinfunction "DRAIN_2") (pintype "passive"))
    )
    (net (code "6") (name "7_4V_TOP2") (class "Default")
      (node (ref "LED1_CONN") (pin "2") (pinfunction "2_2") (pintype "passive"))
      (node (ref "LED2_CONN") (pin "2") (pinfunction "2_2") (pintype "passive"))
      (node (ref "R6") (pin "P$2") (pinfunction "2_P$2") (pintype "passive"))
      (node (ref "R8") (pin "P$2") (pinfunction "2_P$2") (pintype "passive"))
      (node (ref "SV7") (pin "1") (pinfunction "1_1") (pintype "passive"))
      (node (ref "SV9") (pin "2") (pinfunction "2_2") (pintype "passive"))
    )
    (net (code "7") (name "ADC6") (class "Default")
      (node (ref "ATGPIO") (pin "6") (pinfunction "6_6") (pintype "passive"))
      (node (ref "U7") (pin "19") (pinfunction "ADC6_19") (pintype "bidirectional"))
    )
    (net (code "8") (name "ADC7") (class "Default")
      (node (ref "ATGPIO") (pin "7") (pinfunction "7_7") (pintype "passive"))
      (node (ref "U7") (pin "22") (pinfunction "ADC7_22") (pintype "bidirectional"))
    )
    (net (code "9") (name "BATT_VOLTAGE") (class "Default")
      (node (ref "BATT_HIGH") (pin "MP") (pinfunction "MP_MP") (pintype "passive"))
      (node (ref "FUSE") (pin "A") (pinfunction "VCC_A") (pintype "power_in"))
      (node (ref "FUSE") (pin "C") (pinfunction "VCC_C") (pintype "power_in"))
    )
    (net (code "10") (name "BATT_VOLTAGE_SENSE") (class "Default")
      (node (ref "R1") (pin "1") (pinfunction "1_1") (pintype "passive"))
      (node (ref "R2") (pin "2") (pinfunction "2_2") (pintype "passive"))
      (node (ref "U$1") (pin "17/A3") (pinfunction "17/A3_17/A3") (pintype "bidirectional"))
    )
    (net (code "11") (name "BLT_RX") (class "Default")
      (node (ref "BLUETOOTH") (pin "1") (pinfunction "1_1") (pintype "passive"))
      (node (ref "U$1") (pin "8") (pinfunction "8_8") (pintype "bidirectional"))
    )
    (net (code "12") (name "BLT_TX") (class "Default")
      (node (ref "BLUETOOTH") (pin "2") (pinfunction "2_2") (pintype "passive"))
      (node (ref "U$1") (pin "7") (pinfunction "7_7") (pintype "bidirectional"))
    )
    (net (code "13") (name "CAMERA_A0") (class "Default")
      (node (ref "CAMERA") (pin "3") (pinfunction "3_3") (pintype "passive"))
      (node (ref "U7") (pin "23") (pinfunction "PC0(ADC0)_23") (pintype "bidirectional"))
    )
    (net (code "14") (name "CAMERA_A0_B") (class "Default")
      (node (ref "CAMERA_B") (pin "3") (pinfunction "3_3") (pintype "passive"))
      (node (ref "U$1") (pin "31/A12") (pinfunction "31/A12_31/A12") (pintype "bidirectional"))
    )
    (net (code "15") (name "CAMERA_CL") (class "Default")
      (node (ref "CAMERA") (pin "4") (pinfunction "4_4") (pintype "passive"))
      (node (ref "U7") (pin "12") (pinfunction "PB0(ICP)_12") (pintype "bidirectional"))
    )
    (net (code "16") (name "CAMERA_CL_B") (class "Default")
      (node (ref "CAMERA_B") (pin "4") (pinfunction "4_4") (pintype "passive"))
      (node (ref "U$1") (pin "30") (pinfunction "30_30") (pintype "bidirectional"))
    )
    (net (code "17") (name "CAMERA_SI") (class "Default")
      (node (ref "CAMERA") (pin "5") (pinfunction "5_5") (pintype "passive"))
      (node (ref "U7") (pin "11") (pinfunction "PD7(AIN1)_11") (pintype "bidirectional"))
    )
    (net (code "18") (name "CAMERA_SI_B") (class "Default")
      (node (ref "CAMERA_B") (pin "5") (pinfunction "5_5") (pintype "passive"))
      (node (ref "U$1") (pin "29") (pinfunction "29_29") (pintype "bidirectional"))
    )
    (net (code "19") (name "EMF_SENSE_HIGH") (class "Default")
      (node (ref "R3") (pin "1") (pinfunction "1_1") (pintype "passive"))
      (node (ref "R4") (pin "2") (pinfunction "2_2") (pintype "passive"))
      (node (ref "U$1") (pin "19/A5/SCL") (pinfunction "19/A5/SCL_19/A5/SCL") (pintype "bidirectional"))
    )
    (net (code "20") (name "EMF_SENSE_LOW") (class "Default")
      (node (ref "S1") (pin "5") (pinfunction "5_5") (pintype "passive"))
      (node (ref "U$1") (pin "18/A4/SDA") (pinfunction "18/A4/SDA_18/A4/SDA") (pintype "bidirectional"))
    )
    (net (code "21") (name "GND") (class "Default")
      (node (ref "BLUETOOTH") (pin "3") (pinfunction "3_3") (pintype "passive"))
      (node (ref "C5") (pin "2") (pinfunction "2_2") (pintype "passive"))
      (node (ref "C6") (pin "2") (pinfunction "2_2") (pintype "passive"))
      (node (ref "C8") (pin "2") (pinfunction "2_2") (pintype "passive"))
      (node (ref "CAMERA") (pin "1") (pinfunction "1_1") (pintype "passive"))
      (node (ref "CAMERA_B") (pin "1") (pinfunction "1_1") (pintype "passive"))
      (node (ref "D1") (pin "C") (pinfunction "C_C") (pintype "passive"))
      (node (ref "D2") (pin "C") (pinfunction "C_C") (pintype "passive"))
      (node (ref "D5") (pin "C") (pinfunction "C_C") (pintype "passive"))
      (node (ref "GROUND") (pin "1") (pinfunction "1_1") (pintype "passive"))
      (node (ref "GROUND") (pin "2") (pinfunction "2_2") (pintype "passive"))
      (node (ref "GROUND") (pin "3") (pinfunction "3_3") (pintype "passive"))
      (node (ref "GROUND") (pin "4") (pinfunction "4_4") (pintype "passive"))
      (node (ref "GROUND") (pin "5") (pinfunction "5_5") (pintype "passive"))
      (node (ref "HALL1") (pin "2") (pinfunction "2_2") (pintype "passive"))
      (node (ref "HALL1_B") (pin "2") (pinfunction "2_2") (pintype "passive"))
      (node (ref "HALL2") (pin "2") (pinfunction "2_2") (pintype "passive"))
      (node (ref "HALL2_B") (pin "2") (pinfunction "2_2") (pintype "passive"))
      (node (ref "R2") (pin "1") (pinfunction "1_1") (pintype "passive"))
      (node (ref "REC") (pin "1") (pinfunction "1_1") (pintype "passive"))
      (node (ref "S1") (pin "10") (pinfunction "10_10") (pintype "passive"))
      (node (ref "S1") (pin "11") (pinfunction "11_11") (pintype "passive"))
      (node (ref "S1") (pin "12") (pinfunction "12_12") (pintype "passive"))
      (node (ref "S1") (pin "9") (pinfunction "9_9") (pintype "passive"))
      (node (ref "SERVO") (pin "1") (pinfunction "1_1") (pintype "passive"))
      (node (ref "SV1") (pin "10") (pinfunction "10_10") (pintype "passive"))
      (node (ref "SV1") (pin "7") (pinfunction "7_7") (pintype "passive"))
      (node (ref "SV1") (pin "8") (pinfunction "8_8") (pintype "passive"))
      (node (ref "SV1") (pin "9") (pinfunction "9_9") (pintype "passive"))
      (node (ref "SV3") (pin "4") (pinfunction "4_4") (pintype "passive"))
      (node (ref "U$1") (pin "AGND") (pinfunction "AGND_AGND") (pintype "bidirectional"))
      (node (ref "U$1") (pin "GND") (pinfunction "GND_GND") (pintype "bidirectional"))
      (node (ref "U$1") (pin "GND2") (pinfunction "GND2_GND2") (pintype "bidirectional"))
      (node (ref "U7") (pin "21") (pinfunction "AGND_21") (pintype "bidirectional"))
      (node (ref "U7") (pin "3") (pinfunction "GND_3") (pintype "bidirectional"))
      (node (ref "U7") (pin "5") (pinfunction "GND_5") (pintype "bidirectional"))
      (node (ref "VOLT_REG") (pin "1") (pinfunction "GND_1") (pintype "input"))
    )
    (net (code "22") (name "GND_TOP") (class "Default")
      (node (ref "BATT_LOW") (pin "MP") (pinfunction "MP_MP") (pintype "passive"))
      (node (ref "BOT_FWD") (pin "3") (pinfunction "SOURCE_3") (pintype "passive"))
      (node (ref "BOT_REV") (pin "3") (pinfunction "SOURCE_3") (pintype "passive"))
      (node (ref "C12") (pin "-") (pinfunction "-_-") (pintype "passive"))
      (node (ref "C13") (pin "-") (pinfunction "-_-") (pintype "passive"))
      (node (ref "C14") (pin "-") (pinfunction "-_-") (pintype "passive"))
      (node (ref "C15") (pin "-") (pinfunction "-_-") (pintype "passive"))
      (node (ref "C7") (pin "2") (pinfunction "2_2") (pintype "passive"))
      (node (ref "GATE1") (pin "7") (pinfunction "VSS_7") (pintype "power_in"))
      (node (ref "GATE2") (pin "7") (pinfunction "VSS_7") (pintype "power_in"))
      (node (ref "I_SENSE_AMP") (pin "2") (pinfunction "V-_2") (pintype "power_in"))
      (node (ref "MOTOR_NEG_B") (pin "MP") (pinfunction "MP_MP") (pintype "passive"))
      (node (ref "R16") (pin "1") (pinfunction "1_1") (pintype "passive"))
      (node (ref "R18") (pin "1") (pinfunction "1_1") (pintype "passive"))
      (node (ref "SV5") (pin "10") (pinfunction "10_10") (pintype "passive"))
      (node (ref "SV5") (pin "7") (pinfunction "7_7") (pintype "passive"))
      (node (ref "SV5") (pin "8") (pinfunction "8_8") (pintype "passive"))
      (node (ref "SV5") (pin "9") (pinfunction "9_9") (pintype "passive"))
    )
    (net (code "23") (name "GND_TOP2") (class "Default")
      (node (ref "SV7") (pin "4") (pinfunction "4_4") (pintype "passive"))
      (node (ref "SV9") (pin "1") (pinfunction "1_1") (pintype "passive"))
      (node (ref "T1") (pin "1") (pinfunction "E_1") (pintype "passive"))
      (node (ref "T2") (pin "1") (pinfunction "E_1") (pintype "passive"))
      (node (ref "U$3") (pin "P2") (pinfunction "P2_P2") (pintype "bidirectional"))
      (node (ref "U$7") (pin "P2") (pinfunction "P2_P2") (pintype "bidirectional"))
    )
    (net (code "24") (name "HALL1") (class "Default")
      (node (ref "HALL1") (pin "3") (pinfunction "3_3") (pintype "passive"))
      (node (ref "R12") (pin "2") (pinfunction "2_2") (pintype "passive"))
      (node (ref "U7") (pin "32") (pinfunction "PD2(INT0)_32") (pintype "bidirectional"))
    )
    (net (code "25") (name "HALL1_B") (class "Default")
      (node (ref "HALL1_B") (pin "3") (pinfunction "3_3") (pintype "passive"))
      (node (ref "R14") (pin "2") (pinfunction "2_2") (pintype "passive"))
      (node (ref "U$1") (pin "1/TX") (pinfunction "1/TX_1/TX") (pintype "bidirectional"))
    )
    (net (code "26") (name "HALL2") (class "Default")
      (node (ref "HALL2") (pin "3") (pinfunction "3_3") (pintype "passive"))
      (node (ref "R13") (pin "2") (pinfunction "2_2") (pintype "passive"))
      (node (ref "U7") (pin "1") (pinfunction "PD3(INT1)_1") (pintype "bidirectional"))
    )
    (net (code "27") (name "HALL2_B") (class "Default")
      (node (ref "HALL2_B") (pin "3") (pinfunction "3_3") (pintype "passive"))
      (node (ref "R15") (pin "2") (pinfunction "2_2") (pintype "passive"))
      (node (ref "U$1") (pin "2") (pinfunction "2_2") (pintype "bidirectional"))
    )
    (net (code "28") (name "HI") (class "Default")
      (node (ref "SV2") (pin "2") (pinfunction "2_2") (pintype "passive"))
      (node (ref "U$1") (pin "3/CANTX") (pinfunction "3/CANTX_3/CANTX") (pintype "bidirectional"))
    )
    (net (code "29") (name "HI_TOP") (class "Default")
      (node (ref "GATE1") (pin "5") (pinfunction "HI_5") (pintype "input"))
      (node (ref "GATE2") (pin "6") (pinfunction "LI_6") (pintype "input"))
      (node (ref "SV6") (pin "2") (pinfunction "2_2") (pintype "passive"))
    )
    (net (code "30") (name "I_SENSE") (class "Default")
      (node (ref "SV2") (pin "3") (pinfunction "3_3") (pintype "passive"))
      (node (ref "U$1") (pin "5") (pinfunction "5_5") (pintype "bidirectional"))
    )
    (net (code "31") (name "I_SENSE_HI_TOP") (class "Default")
      (node (ref "BOT_REV") (pin "2") (pinfunction "DRAIN_2") (pintype "passive"))
      (node (ref "I_SENSE_AMP") (pin "3") (pinfunction "IN+_3") (pintype "input"))
      (node (ref "R17") (pin "1") (pinfunction "1_1") (pintype "passive"))
      (node (ref "TOP_FWD") (pin "3") (pinfunction "SOURCE_3") (pintype "passive"))
    )
    (net (code "32") (name "I_SENSE_LOW_TOP") (class "Default")
      (node (ref "I_SENSE_AMP") (pin "4") (pinfunction "IN-_4") (pintype "input"))
      (node (ref "MOTOR_POS") (pin "MP") (pinfunction "MP_MP") (pintype "passive"))
      (node (ref "R17") (pin "2") (pinfunction "2_2") (pintype "passive"))
      (node (ref "SV6") (pin "5") (pinfunction "5_5") (pintype "passive"))
    )
    (net (code "33") (name "I_SENSE_TOP") (class "Default")
      (node (ref "I_SENSE_AMP") (pin "1") (pinfunction "OUT_1") (pintype "output"))
      (node (ref "R18") (pin "2") (pinfunction "2_2") (pintype "passive"))
      (node (ref "SV6") (pin "3") (pinfunction "3_3") (pintype "passive"))
    )
    (net (code "34") (name "LED1") (class "Default")
      (node (ref "R9") (pin "2") (pinfunction "2_2") (pintype "passive"))
      (node (ref "U$1") (pin "14/A0") (pinfunction "14/A0_14/A0") (pintype "bidirectional"))
    )
    (net (code "35") (name "LED1HI") (class "Default")
      (node (ref "LED1") (pin "POSITIVE") (pinfunction "POSITIVE_POSITIVE") (pintype "bidirectional"))
      (node (ref "LED1") (pin "POSITIVE1") (pinfunction "POSITIVE_POSITIVE1") (pintype "bidirectional"))
      (node (ref "LED1_CONN2") (pin "2") (pinfunction "2_2") (pintype "passive"))
    )
    (net (code "36") (name "LED1LO") (class "Default")
      (node (ref "LED1") (pin "NEGATIVE") (pinfunction "NEGATIVE_NEGATIVE") (pintype "bidirectional"))
      (node (ref "LED1") (pin "NEGATIVE1") (pinfunction "NEGATIVE_NEGATIVE1") (pintype "bidirectional"))
      (node (ref "LED1_CONN2") (pin "1") (pinfunction "1_1") (pintype "passive"))
    )
    (net (code "37") (name "LED2") (class "Default")
      (node (ref "R10") (pin "2") (pinfunction "2_2") (pintype "passive"))
      (node (ref "U$1") (pin "15/A1") (pinfunction "15/A1_15/A1") (pintype "bidirectional"))
    )
    (net (code "38") (name "LED2HI") (class "Default")
      (node (ref "LED2") (pin "POSITIVE") (pinfunction "POSITIVE_POSITIVE") (pintype "bidirectional"))
      (node (ref "LED2") (pin "POSITIVE1") (pinfunction "POSITIVE_POSITIVE1") (pintype "bidirectional"))
      (node (ref "LED2_CONN2") (pin "2") (pinfunction "2_2") (pintype "passive"))
    )
    (net (code "39") (name "LED2LO") (class "Default")
      (node (ref "LED2") (pin "NEGATIVE") (pinfunction "NEGATIVE_NEGATIVE") (pintype "bidirectional"))
      (node (ref "LED2") (pin "NEGATIVE1") (pinfunction "NEGATIVE_NEGATIVE1") (pintype "bidirectional"))
      (node (ref "LED2_CONN2") (pin "1") (pinfunction "1_1") (pintype "passive"))
    )
    (net (code "40") (name "LED3") (class "Default")
      (node (ref "R11") (pin "2") (pinfunction "2_2") (pintype "passive"))
      (node (ref "U$1") (pin "16/A2") (pinfunction "16/A2_16/A2") (pintype "bidirectional"))
    )
    (net (code "41") (name "LI") (class "Default")
      (node (ref "SV2") (pin "1") (pinfunction "1_1") (pintype "passive"))
      (node (ref "U$1") (pin "4/CANRX") (pinfunction "4/CANRX_4/CANRX") (pintype "bidirectional"))
    )
    (net (code "42") (name "LI_TOP") (class "Default")
      (node (ref "GATE1") (pin "6") (pinfunction "LI_6") (pintype "input"))
      (node (ref "GATE2") (pin "5") (pinfunction "HI_5") (pintype "input"))
      (node (ref "SV6") (pin "1") (pinfunction "1_1") (pintype "passive"))
    )
    (net (code "43") (name "MOTOR_HIGH") (class "Default")
      (node (ref "R3") (pin "2") (pinfunction "2_2") (pintype "passive"))
      (node (ref "SV2") (pin "5") (pinfunction "5_5") (pintype "passive"))
    )
    (net (code "44") (name "MOTOR_LOW") (class "Default")
      (node (ref "R4") (pin "1") (pinfunction "1_1") (pintype "passive"))
      (node (ref "S1") (pin "8") (pinfunction "8_8") (pintype "passive"))
      (node (ref "SV2") (pin "6") (pinfunction "6_6") (pintype "passive"))
    )
    (net (code "45") (name "MOTOR_LOW_TOP") (class "Default")
      (node (ref "BOT_FWD") (pin "2") (pinfunction "DRAIN_2") (pintype "passive"))
      (node (ref "MOTOR_NEG") (pin "MP") (pinfunction "MP_MP") (pintype "passive"))
      (node (ref "SV6") (pin "6") (pinfunction "6_6") (pintype "passive"))
      (node (ref "TOP_REV") (pin "3") (pinfunction "SOURCE_3") (pintype "passive"))
    )
    (net (code "46") (name "Net-(BIG_SWITCH-PadVCC)") (class "Default")
      (node (ref "BIG_SWITCH") (pin "VCC") (pinfunction "VCC_VCC") (pintype "power_in"))
      (node (ref "C12") (pin "+") (pinfunction "+_+") (pintype "passive"))
      (node (ref "C13") (pin "+") (pinfunction "+_+") (pintype "passive"))
      (node (ref "C14") (pin "+") (pinfunction "+_+") (pintype "passive"))
      (node (ref "C15") (pin "+") (pinfunction "+_+") (pintype "passive"))
      (node (ref "FUSE") (pin "B") (pinfunction "GND_B") (pintype "power_in"))
      (node (ref "FUSE") (pin "D") (pinfunction "GND_D") (pintype "power_in"))
      (node (ref "R16") (pin "2") (pinfunction "2_2") (pintype "passive"))
    )
    (net (code "47") (name "Net-(BOT_FWD-GATE)") (class "Default")
      (node (ref "BOT_FWD") (pin "1") (pinfunction "GATE_1") (pintype "passive"))
      (node (ref "GATE2") (pin "8") (pinfunction "LO_8") (pintype "output"))
    )
    (net (code "48") (name "Net-(BOT_REV-GATE)") (class "Default")
      (node (ref "BOT_REV") (pin "1") (pinfunction "GATE_1") (pintype "passive"))
      (node (ref "GATE1") (pin "8") (pinfunction "LO_8") (pintype "output"))
    )
    (net (code "49") (name "Net-(D1-PadA)") (class "Default")
      (node (ref "D1") (pin "A") (pinfunction "A_A") (pintype "passive"))
      (node (ref "R9") (pin "1") (pinfunction "1_1") (pintype "passive"))
    )
    (net (code "50") (name "Net-(D2-PadA)") (class "Default")
      (node (ref "D2") (pin "A") (pinfunction "A_A") (pintype "passive"))
      (node (ref "R10") (pin "1") (pinfunction "1_1") (pintype "passive"))
    )
    (net (code "51") (name "Net-(D5-PadA)") (class "Default")
      (node (ref "D5") (pin "A") (pinfunction "A_A") (pintype "passive"))
      (node (ref "R11") (pin "1") (pinfunction "1_1") (pintype "passive"))
    )
    (net (code "52") (name "Net-(GATE1-HB)") (class "Default")
      (node (ref "C1") (pin "2") (pinfunction "2_2") (pintype "passive"))
      (node (ref "C2") (pin "2") (pinfunction "2_2") (pintype "passive"))
      (node (ref "D3") (pin "C") (pinfunction "C_C") (pintype "passive"))
      (node (ref "GATE1") (pin "2") (pinfunction "HB_2") (pintype "passive"))
    )
    (net (code "53") (name "Net-(GATE1-HO)") (class "Default")
      (node (ref "GATE1") (pin "3") (pinfunction "HO_3") (pintype "output"))
      (node (ref "TOP_FWD") (pin "1") (pinfunction "GATE_1") (pintype "passive"))
    )
    (net (code "54") (name "Net-(GATE1-HS)") (class "Default")
      (node (ref "C1") (pin "1") (pinfunction "1_1") (pintype "passive"))
      (node (ref "C2") (pin "1") (pinfunction "1_1") (pintype "passive"))
      (node (ref "GATE1") (pin "4") (pinfunction "HS_4") (pintype "passive"))
    )
    (net (code "55") (name "Net-(GATE2-HB)") (class "Default")
      (node (ref "C3") (pin "2") (pinfunction "2_2") (pintype "passive"))
      (node (ref "C4") (pin "2") (pinfunction "2_2") (pintype "passive"))
      (node (ref "D4") (pin "C") (pinfunction "C_C") (pintype "passive"))
      (node (ref "GATE2") (pin "2") (pinfunction "HB_2") (pintype "passive"))
    )
    (net (code "56") (name "Net-(GATE2-HO)") (class "Default")
      (node (ref "GATE2") (pin "3") (pinfunction "HO_3") (pintype "output"))
      (node (ref "TOP_REV") (pin "1") (pinfunction "GATE_1") (pintype "passive"))
    )
    (net (code "57") (name "Net-(GATE2-HS)") (class "Default")
      (node (ref "C3") (pin "1") (pinfunction "1_1") (pintype "passive"))
      (node (ref "C4") (pin "1") (pinfunction "1_1") (pintype "passive"))
      (node (ref "GATE2") (pin "4") (pinfunction "HS_4") (pintype "passive"))
    )
    (net (code "58") (name "Net-(LED_DRIVER1-DRAIN)") (class "Default")
      (node (ref "LED2_CONN") (pin "1") (pinfunction "1_1") (pintype "passive"))
      (node (ref "LED_DRIVER1") (pin "2") (pinfunction "DRAIN_2") (pintype "passive"))
    )
    (net (code "59") (name "Net-(LED_DRIVER1-GATE)") (class "Default")
      (node (ref "LED_DRIVER1") (pin "1") (pinfunction "GATE_1") (pintype "passive"))
      (node (ref "R8") (pin "P$1") (pinfunction "1_P$1") (pintype "passive"))
      (node (ref "T2") (pin "3") (pinfunction "C_3") (pintype "passive"))
    )
    (net (code "60") (name "Net-(LED_DRIVER1-SOURCE)") (class "Default")
      (node (ref "LED_DRIVER1") (pin "3") (pinfunction "SOURCE_3") (pintype "passive"))
      (node (ref "R7") (pin "2") (pinfunction "2_2") (pintype "passive"))
      (node (ref "T2") (pin "2") (pinfunction "B_2") (pintype "passive"))
    )
    (net (code "61") (name "Net-(LED_DRIVER2-DRAIN)") (class "Default")
      (node (ref "LED1_CONN") (pin "1") (pinfunction "1_1") (pintype "passive"))
      (node (ref "LED_DRIVER2") (pin "2") (pinfunction "DRAIN_2") (pintype "passive"))
    )
    (net (code "62") (name "Net-(LED_DRIVER2-GATE)") (class "Default")
      (node (ref "LED_DRIVER2") (pin "1") (pinfunction "GATE_1") (pintype "passive"))
      (node (ref "R6") (pin "P$1") (pinfunction "1_P$1") (pintype "passive"))
      (node (ref "T1") (pin "3") (pinfunction "C_3") (pintype "passive"))
    )
    (net (code "63") (name "Net-(LED_DRIVER2-SOURCE)") (class "Default")
      (node (ref "LED_DRIVER2") (pin "3") (pinfunction "SOURCE_3") (pintype "passive"))
      (node (ref "R5") (pin "2") (pinfunction "2_2") (pintype "passive"))
      (node (ref "T1") (pin "2") (pinfunction "B_2") (pintype "passive"))
    )
    (net (code "64") (name "Net-(R5-Pad1)") (class "Default")
      (node (ref "R5") (pin "1") (pinfunction "1_1") (pintype "passive"))
      (node (ref "U$7") (pin "P3") (pinfunction "P3_P3") (pintype "bidirectional"))
    )
    (net (code "65") (name "Net-(R7-Pad1)") (class "Default")
      (node (ref "R7") (pin "1") (pinfunction "1_1") (pintype "passive"))
      (node (ref "U$3") (pin "P3") (pinfunction "P3_P3") (pintype "bidirectional"))
    )
    (net (code "66") (name "Net-(U7-PB6(XTAL1{slash}TOSC1))") (class "Default")
      (node (ref "C6") (pin "1") (pinfunction "1_1") (pintype "passive"))
      (node (ref "U7") (pin "7") (pinfunction "PB6(XTAL1/TOSC1)_7") (pintype "bidirectional"))
      (node (ref "Y1") (pin "1") (pinfunction "1_1") (pintype "passive"))
    )
    (net (code "67") (name "Net-(U7-PB7(XTAL2{slash}TOSC2))") (class "Default")
      (node (ref "C5") (pin "1") (pinfunction "1_1") (pintype "passive"))
      (node (ref "U7") (pin "8") (pinfunction "PB7(XTAL2/TOSC2)_8") (pintype "bidirectional"))
      (node (ref "Y1") (pin "2") (pinfunction "2_2") (pintype "passive"))
    )
    (net (code "68") (name "PB1") (class "Default")
      (node (ref "ATGPIO") (pin "10") (pinfunction "10_10") (pintype "passive"))
      (node (ref "U7") (pin "13") (pinfunction "PB1(OC1A)_13") (pintype "bidirectional"))
    )
    (net (code "69") (name "PC1") (class "Default")
      (node (ref "ATGPIO") (pin "1") (pinfunction "1_1") (pintype "passive"))
      (node (ref "U7") (pin "24") (pinfunction "PC1(ADC1)_24") (pintype "bidirectional"))
    )
    (net (code "70") (name "PC2") (class "Default")
      (node (ref "ATGPIO") (pin "2") (pinfunction "2_2") (pintype "passive"))
      (node (ref "U7") (pin "25") (pinfunction "PC2(ADC2)_25") (pintype "bidirectional"))
    )
    (net (code "71") (name "PC3") (class "Default")
      (node (ref "ATGPIO") (pin "3") (pinfunction "3_3") (pintype "passive"))
      (node (ref "U7") (pin "26") (pinfunction "PC3(ADC3)_26") (pintype "bidirectional"))
    )
    (net (code "72") (name "PC4") (class "Default")
      (node (ref "ATGPIO") (pin "4") (pinfunction "4_4") (pintype "passive"))
      (node (ref "U7") (pin "27") (pinfunction "PC4(ADC4/SDA)_27") (pintype "bidirectional"))
    )
    (net (code "73") (name "PC5") (class "Default")
      (node (ref "ATGPIO") (pin "5") (pinfunction "5_5") (pintype "passive"))
      (node (ref "U7") (pin "28") (pinfunction "PC5(ADC5/SCL)_28") (pintype "bidirectional"))
    )
    (net (code "74") (name "PD4") (class "Default")
      (node (ref "ATGPIO") (pin "8") (pinfunction "8_8") (pintype "passive"))
      (node (ref "U7") (pin "2") (pinfunction "PD4(XCK/T0)_2") (pintype "bidirectional"))
    )
    (net (code "75") (name "PD5") (class "Default")
      (node (ref "ATGPIO") (pin "9") (pinfunction "9_9") (pintype "passive"))
      (node (ref "U7") (pin "9") (pinfunction "PD5(T1)_9") (pintype "bidirectional"))
    )
    (net (code "76") (name "PD6") (class "Default")
      (node (ref "U7") (pin "10") (pinfunction "PD6(AIN0)_10") (pintype "bidirectional"))
    )
    (net (code "77") (name "REC_EXTRA1") (class "Default")
      (node (ref "REC") (pin "5") (pinfunction "5_5") (pintype "passive"))
      (node (ref "U$1") (pin "22/A8") (pinfunction "22/A8_22/A8") (pintype "bidirectional"))
    )
    (net (code "78") (name "REC_EXTRA2") (class "Default")
      (node (ref "REC") (pin "6") (pinfunction "6_6") (pintype "passive"))
      (node (ref "U$1") (pin "23/A9") (pinfunction "23/A9_23/A9") (pintype "bidirectional"))
    )
    (net (code "79") (name "REC_MOTOR") (class "Default")
      (node (ref "REC") (pin "4") (pinfunction "4_4") (pintype "passive"))
      (node (ref "U$1") (pin "21/A7") (pinfunction "21/A7_21/A7") (pintype "bidirectional"))
    )
    (net (code "80") (name "REC_SERVO") (class "Default")
      (node (ref "REC") (pin "3") (pinfunction "3_3") (pintype "passive"))
      (node (ref "U$1") (pin "20/A6") (pinfunction "20/A6_20/A6") (pintype "bidirectional"))
    )
    (net (code "81") (name "RX") (class "Default")
      (node (ref "TXRX") (pin "1") (pinfunction "1_1") (pintype "passive"))
      (node (ref "U7") (pin "30") (pinfunction "PD0(RXD)_30") (pintype "bidirectional"))
    )
    (net (code "82") (name "SERVO") (class "Default")
      (node (ref "SERVO") (pin "3") (pinfunction "3_3") (pintype "passive"))
      (node (ref "U$1") (pin "9/CS") (pinfunction "9/CS_9/CS") (pintype "bidirectional"))
    )
    (net (code "83") (name "SPI_MISO") (class "Default")
      (node (ref "U$1") (pin "11/MOSI") (pinfunction "11/MOSI_11/MOSI") (pintype "bidirectional"))
      (node (ref "U7") (pin "16") (pinfunction "PB4(MISO)_16") (pintype "bidirectional"))
    )
    (net (code "84") (name "SPI_MOSI") (class "Default")
      (node (ref "U$1") (pin "12/MISO") (pinfunction "12/MISO_12/MISO") (pintype "bidirectional"))
      (node (ref "U7") (pin "15") (pinfunction "PB3(MOSI/OC2)_15") (pintype "bidirectional"))
    )
    (net (code "85") (name "SPI_SCK") (class "Default")
      (node (ref "U$1") (pin "13/SCK") (pinfunction "13/SCK_13/SCK") (pintype "bidirectional"))
      (node (ref "U7") (pin "17") (pinfunction "PB5(SCK)_17") (pintype "bidirectional"))
    )
    (net (code "86") (name "SPI_SS") (class "Default")
      (node (ref "U$1") (pin "10/CS") (pinfunction "10/CS_10/CS") (pintype "bidirectional"))
      (node (ref "U7") (pin "14") (pinfunction "PB2(SS/OC1B)_14") (pintype "bidirectional"))
    )
    (net (code "87") (name "SW1") (class "Default")
      (node (ref "S1") (pin "1") (pinfunction "1_1") (pintype "passive"))
      (node (ref "U$1") (pin "24") (pinfunction "24_24") (pintype "bidirectional"))
    )
    (net (code "88") (name "SW2") (class "Default")
      (node (ref "S1") (pin "2") (pinfunction "2_2") (pintype "passive"))
      (node (ref "U$1") (pin "25") (pinfunction "25_25") (pintype "bidirectional"))
    )
    (net (code "89") (name "SW3") (class "Default")
      (node (ref "S1") (pin "3") (pinfunction "3_3") (pintype "passive"))
      (node (ref "U$1") (pin "26") (pinfunction "26_26") (pintype "bidirectional"))
    )
    (net (code "90") (name "SW4") (class "Default")
      (node (ref "S1") (pin "4") (pinfunction "4_4") (pintype "passive"))
      (node (ref "U$1") (pin "27") (pinfunction "27_27") (pintype "bidirectional"))
    )
    (net (code "91") (name "SW5") (class "Default")
      (node (ref "U$1") (pin "28") (pinfunction "28_28") (pintype "bidirectional"))
    )
    (net (code "92") (name "TGPIO1") (class "Default")
      (node (ref "SV10") (pin "1") (pinfunction "1_1") (pintype "passive"))
      (node (ref "U$1") (pin "33/A14") (pinfunction "33/A14_33/A14") (pintype "bidirectional"))
    )
    (net (code "93") (name "TGPIO2") (class "Default")
      (node (ref "SV10") (pin "2") (pinfunction "2_2") (pintype "passive"))
      (node (ref "U$1") (pin "34/A15") (pinfunction "34/A15_34/A15") (pintype "bidirectional"))
    )
    (net (code "94") (name "TGPIO3") (class "Default")
      (node (ref "SV10") (pin "3") (pinfunction "3_3") (pintype "passive"))
      (node (ref "U$1") (pin "35/A16") (pinfunction "35/A16_35/A16") (pintype "bidirectional"))
    )
    (net (code "95") (name "TGPIO4") (class "Default")
      (node (ref "SV10") (pin "4") (pinfunction "4_4") (pintype "passive"))
      (node (ref "U$1") (pin "36/A17") (pinfunction "36/A17_36/A17") (pintype "bidirectional"))
    )
    (net (code "96") (name "TGPIO5") (class "Default")
      (node (ref "SV10") (pin "5") (pinfunction "5_5") (pintype "passive"))
      (node (ref "U$1") (pin "37/A18") (pinfunction "37/A18_37/A18") (pintype "bidirectional"))
    )
    (net (code "97") (name "TGPIO6") (class "Default")
      (node (ref "SV10") (pin "6") (pinfunction "6_6") (pintype "passive"))
      (node (ref "U$1") (pin "38/A19") (pinfunction "38/A19_38/A19") (pintype "bidirectional"))
    )
    (net (code "98") (name "TGPIO7") (class "Default")
      (node (ref "SV10") (pin "7") (pinfunction "7_7") (pintype "passive"))
      (node (ref "U$1") (pin "39/A20") (pinfunction "39/A20_39/A20") (pintype "bidirectional"))
    )
    (net (code "99") (name "TGPIO8") (class "Default")
      (node (ref "SV10") (pin "8") (pinfunction "8_8") (pintype "passive"))
      (node (ref "U$1") (pin "21/DAC0") (pinfunction "A21/DAC0_21/DAC0") (pintype "bidirectional"))
    )
    (net (code "100") (name "TGPIO9") (class "Default")
      (node (ref "SV10") (pin "9") (pinfunction "9_9") (pintype "passive"))
      (node (ref "U$1") (pin "A22/DAC1") (pinfunction "A22/DAC1_A22/DAC1") (pintype "bidirectional"))
    )
    (net (code "101") (name "THERM2") (class "Default")
      (node (ref "LED2") (pin "THERMAL") (pinfunction "THERMAL_THERMAL") (pintype "bidirectional"))
    )
    (net (code "102") (name "TX") (class "Default")
      (node (ref "TXRX") (pin "2") (pinfunction "2_2") (pintype "passive"))
      (node (ref "U7") (pin "31") (pinfunction "PD1(TXD)_31") (pintype "bidirectional"))
    )
    (net (code "103") (name "unconnected-(LED1-PadTHERMAL)") (class "Default")
      (node (ref "LED1") (pin "THERMAL") (pinfunction "THERMAL_THERMAL") (pintype "bidirectional"))
    )
    (net (code "104") (name "unconnected-(SV1-Pad1)") (class "Default")
      (node (ref "SV1") (pin "1") (pinfunction "1_1") (pintype "passive"))
    )
    (net (code "105") (name "unconnected-(SV1-Pad2)") (class "Default")
      (node (ref "SV1") (pin "2") (pinfunction "2_2") (pintype "passive"))
    )
    (net (code "106") (name "unconnected-(SV2-Pad4)") (class "Default")
      (node (ref "SV2") (pin "4") (pinfunction "4_4") (pintype "passive"))
    )
    (net (code "107") (name "unconnected-(SV2-Pad7)") (class "Default")
      (node (ref "SV2") (pin "7") (pinfunction "7_7") (pintype "passive"))
    )
    (net (code "108") (name "unconnected-(SV2-Pad8)") (class "Default")
      (node (ref "SV2") (pin "8") (pinfunction "8_8") (pintype "passive"))
    )
    (net (code "109") (name "unconnected-(SV2-Pad9)") (class "Default")
      (node (ref "SV2") (pin "9") (pinfunction "9_9") (pintype "passive"))
    )
    (net (code "110") (name "unconnected-(SV2-Pad10)") (class "Default")
      (node (ref "SV2") (pin "10") (pinfunction "10_10") (pintype "passive"))
    )
    (net (code "111") (name "unconnected-(SV3-Pad2)") (class "Default")
      (node (ref "SV3") (pin "2") (pinfunction "2_2") (pintype "passive"))
    )
    (net (code "112") (name "unconnected-(SV3-Pad3)") (class "Default")
      (node (ref "SV3") (pin "3") (pinfunction "3_3") (pintype "passive"))
    )
    (net (code "113") (name "unconnected-(SV4-Pad1)") (class "Default")
      (node (ref "SV4") (pin "1") (pinfunction "1_1") (pintype "passive"))
    )
    (net (code "114") (name "unconnected-(SV4-Pad2)") (class "Default")
      (node (ref "SV4") (pin "2") (pinfunction "2_2") (pintype "passive"))
    )
    (net (code "115") (name "unconnected-(SV4-Pad3)") (class "Default")
      (node (ref "SV4") (pin "3") (pinfunction "3_3") (pintype "passive"))
    )
    (net (code "116") (name "unconnected-(SV4-Pad4)") (class "Default")
      (node (ref "SV4") (pin "4") (pinfunction "4_4") (pintype "passive"))
    )
    (net (code "117") (name "unconnected-(SV5-Pad1)") (class "Default")
      (node (ref "SV5") (pin "1") (pinfunction "1_1") (pintype "passive"))
    )
    (net (code "118") (name "unconnected-(SV5-Pad2)") (class "Default")
      (node (ref "SV5") (pin "2") (pinfunction "2_2") (pintype "passive"))
    )
    (net (code "119") (name "unconnected-(SV6-Pad4)") (class "Default")
      (node (ref "SV6") (pin "4") (pinfunction "4_4") (pintype "passive"))
    )
    (net (code "120") (name "unconnected-(SV6-Pad7)") (class "Default")
      (node (ref "SV6") (pin "7") (pinfunction "7_7") (pintype "passive"))
    )
    (net (code "121") (name "unconnected-(SV6-Pad8)") (class "Default")
      (node (ref "SV6") (pin "8") (pinfunction "8_8") (pintype "passive"))
    )
    (net (code "122") (name "unconnected-(SV6-Pad9)") (class "Default")
      (node (ref "SV6") (pin "9") (pinfunction "9_9") (pintype "passive"))
    )
    (net (code "123") (name "unconnected-(SV6-Pad10)") (class "Default")
      (node (ref "SV6") (pin "10") (pinfunction "10_10") (pintype "passive"))
    )
    (net (code "124") (name "unconnected-(SV7-Pad2)") (class "Default")
      (node (ref "SV7") (pin "2") (pinfunction "2_2") (pintype "passive"))
    )
    (net (code "125") (name "unconnected-(SV7-Pad3)") (class "Default")
      (node (ref "SV7") (pin "3") (pinfunction "3_3") (pintype "passive"))
    )
    (net (code "126") (name "unconnected-(SV8-Pad1)") (class "Default")
      (node (ref "SV8") (pin "1") (pinfunction "1_1") (pintype "passive"))
    )
    (net (code "127") (name "unconnected-(SV8-Pad2)") (class "Default")
      (node (ref "SV8") (pin "2") (pinfunction "2_2") (pintype "passive"))
    )
    (net (code "128") (name "unconnected-(SV8-Pad3)") (class "Default")
      (node (ref "SV8") (pin "3") (pinfunction "3_3") (pintype "passive"))
    )
    (net (code "129") (name "unconnected-(SV8-Pad4)") (class "Default")
      (node (ref "SV8") (pin "4") (pinfunction "4_4") (pintype "passive"))
    )
    (net (code "130") (name "unconnected-(U$1-Pad0{slash}RX)") (class "Default")
      (node (ref "U$1") (pin "0/RX") (pinfunction "0/RX_0/RX") (pintype "bidirectional"))
    )
    (net (code "131") (name "unconnected-(U$1-Pad3V3)") (class "Default")
      (node (ref "U$1") (pin "3V3") (pinfunction "3V3_3V3") (pintype "bidirectional"))
    )
    (net (code "132") (name "unconnected-(U$1-Pad6)") (class "Default")
      (node (ref "U$1") (pin "6") (pinfunction "6_6") (pintype "bidirectional"))
    )
    (net (code "133") (name "unconnected-(U$1-Pad32{slash}A13)") (class "Default")
      (node (ref "U$1") (pin "32/A13") (pinfunction "32/A13_32/A13") (pintype "bidirectional"))
    )
    (net (code "134") (name "unconnected-(U$1-PadA10)") (class "Default")
      (node (ref "U$1") (pin "A10") (pinfunction "A10_A10") (pintype "bidirectional"))
    )
    (net (code "135") (name "unconnected-(U$1-PadA11)") (class "Default")
      (node (ref "U$1") (pin "A11") (pinfunction "A11_A11") (pintype "bidirectional"))
    )
    (net (code "136") (name "unconnected-(U$1-PadAREF)") (class "Default")
      (node (ref "U$1") (pin "AREF") (pinfunction "AREF_AREF") (pintype "bidirectional"))
    )
    (net (code "137") (name "unconnected-(U$1-PadVUSB)") (class "Default")
      (node (ref "U$1") (pin "VUSB") (pinfunction "VUSB_VUSB") (pintype "bidirectional"))
    )
    (net (code "138") (name "unconnected-(U$3-PadP1)") (class "Default")
      (node (ref "U$3") (pin "P1") (pinfunction "P1_P1") (pintype "bidirectional"))
    )
    (net (code "139") (name "unconnected-(U$7-PadP1)") (class "Default")
      (node (ref "U$7") (pin "P1") (pinfunction "P1_P1") (pintype "bidirectional"))
    )
    (net (code "140") (name "unconnected-(U7-AREF-Pad20)") (class "Default")
      (node (ref "U7") (pin "20") (pinfunction "AREF_20") (pintype "bidirectional"))
    )
  )
)
